# io-board-b-4.net
KiCad netlist of a schematic drawn in EAGLE
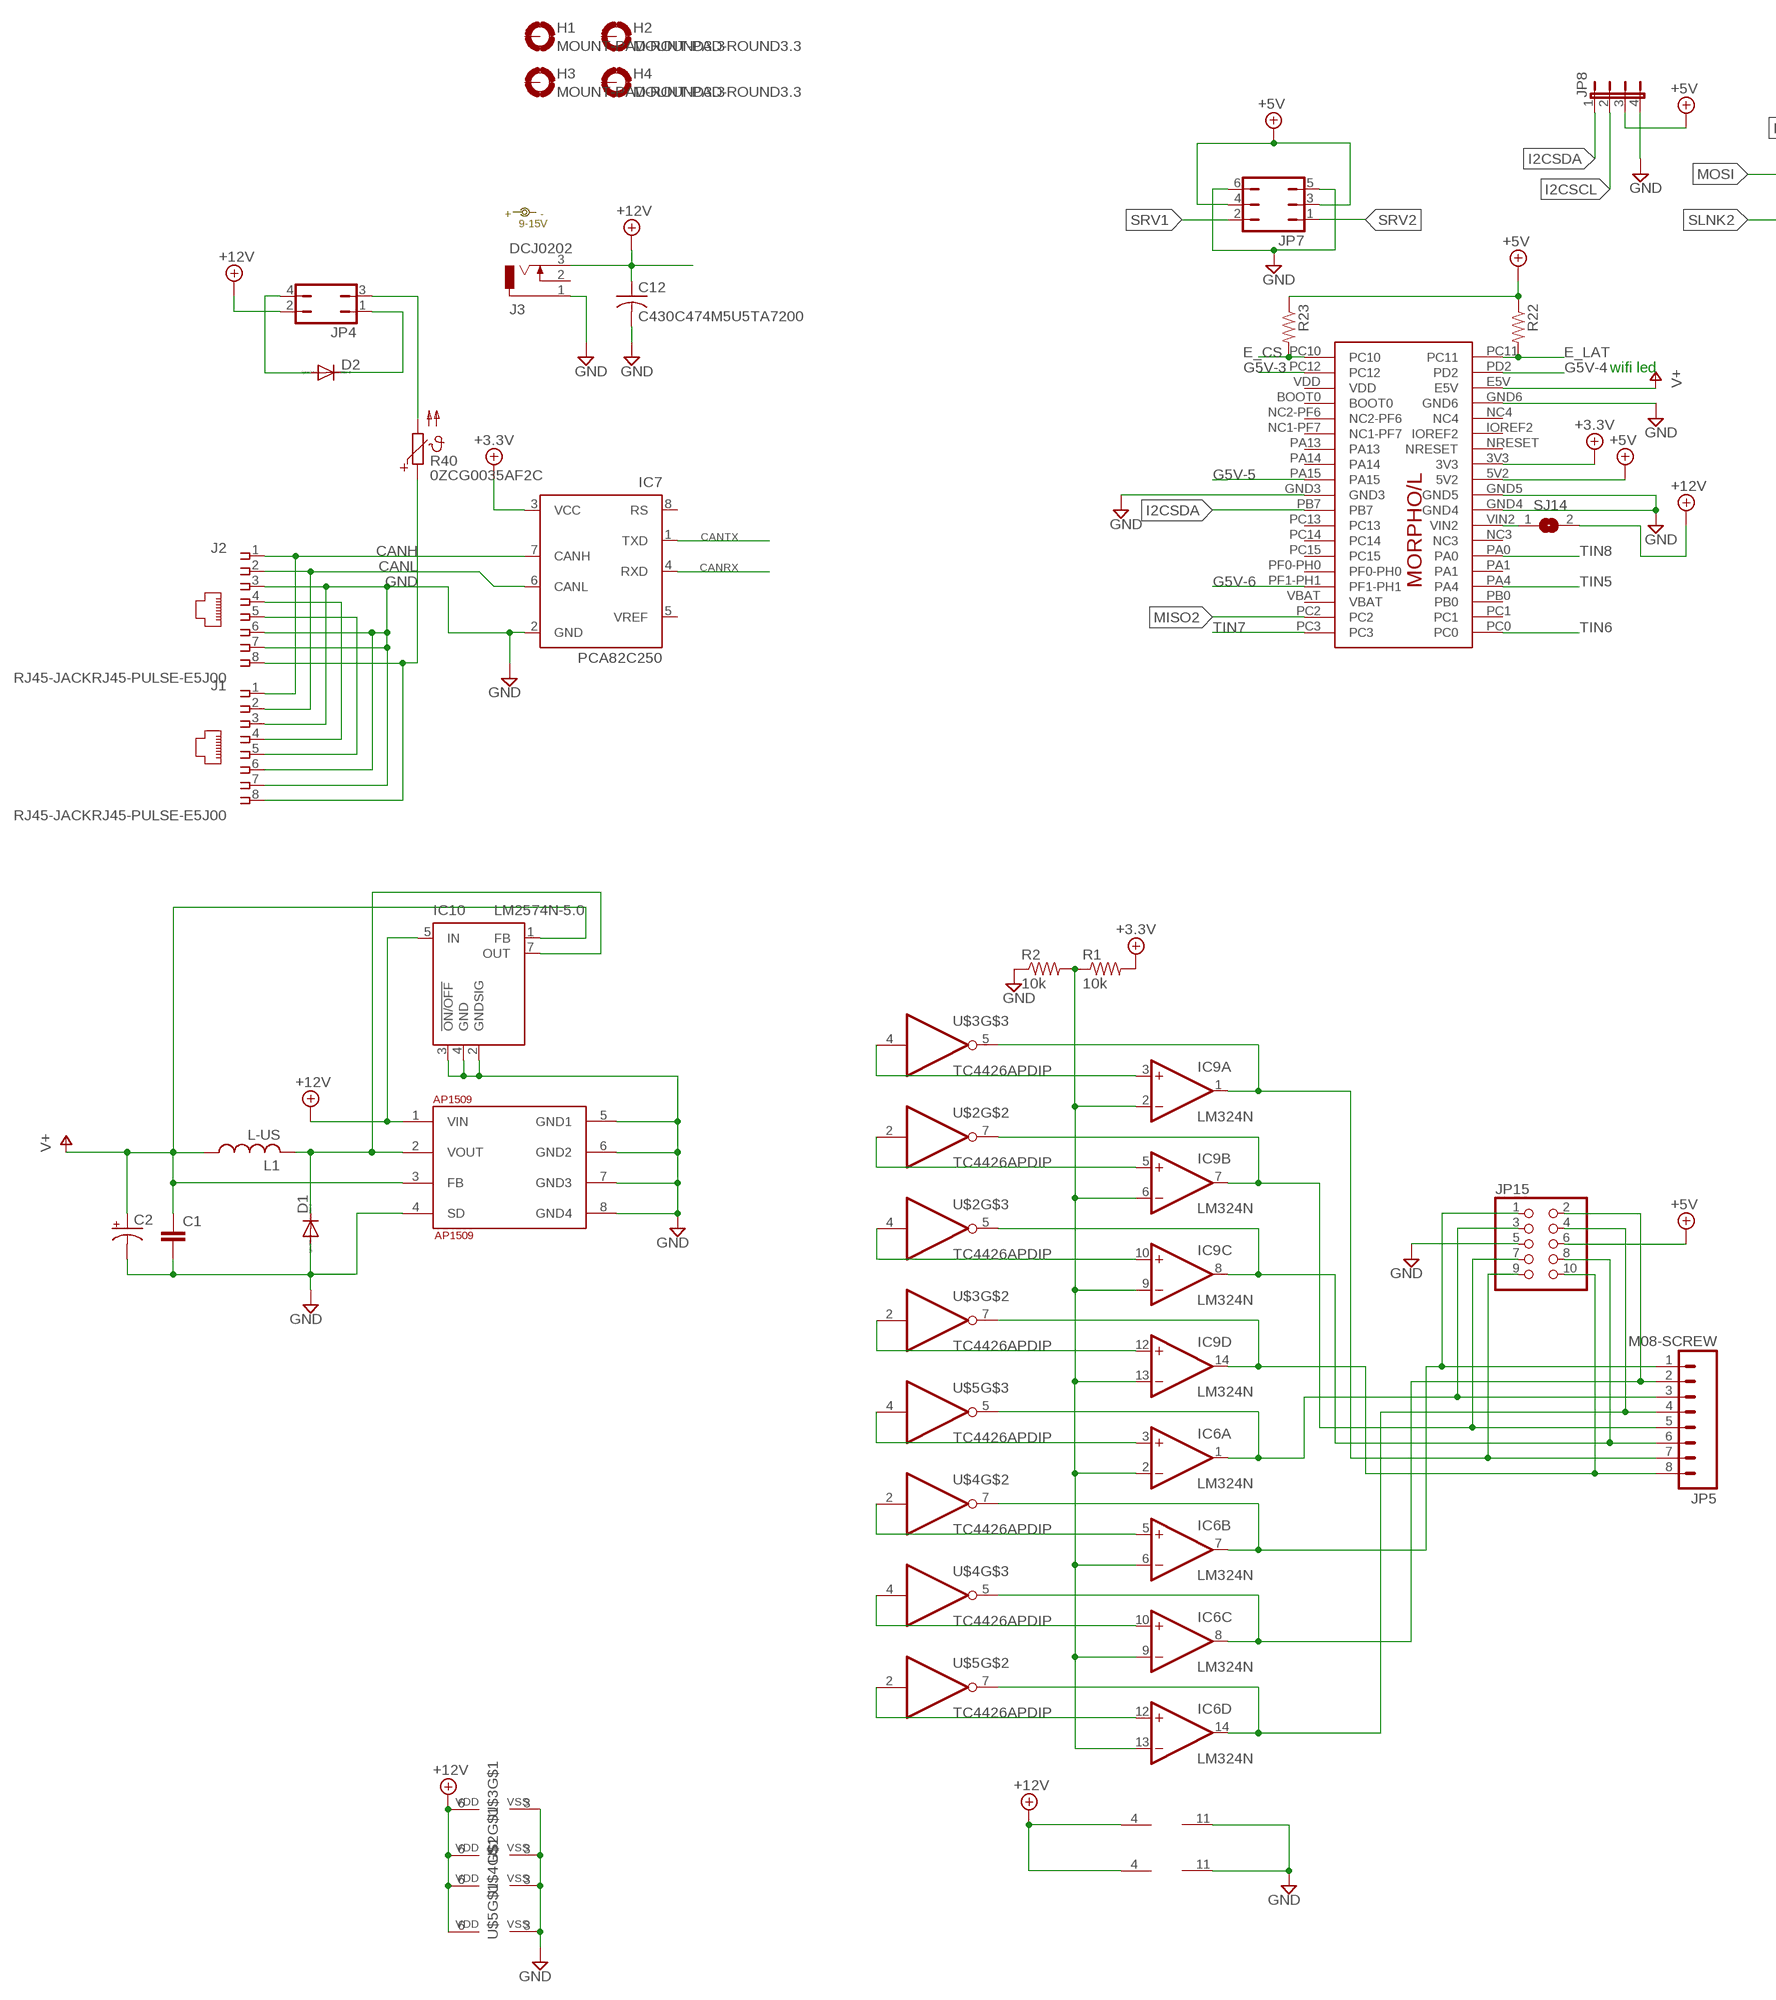
[diagram p0: schematic, sheet 1, part 1 of 2]
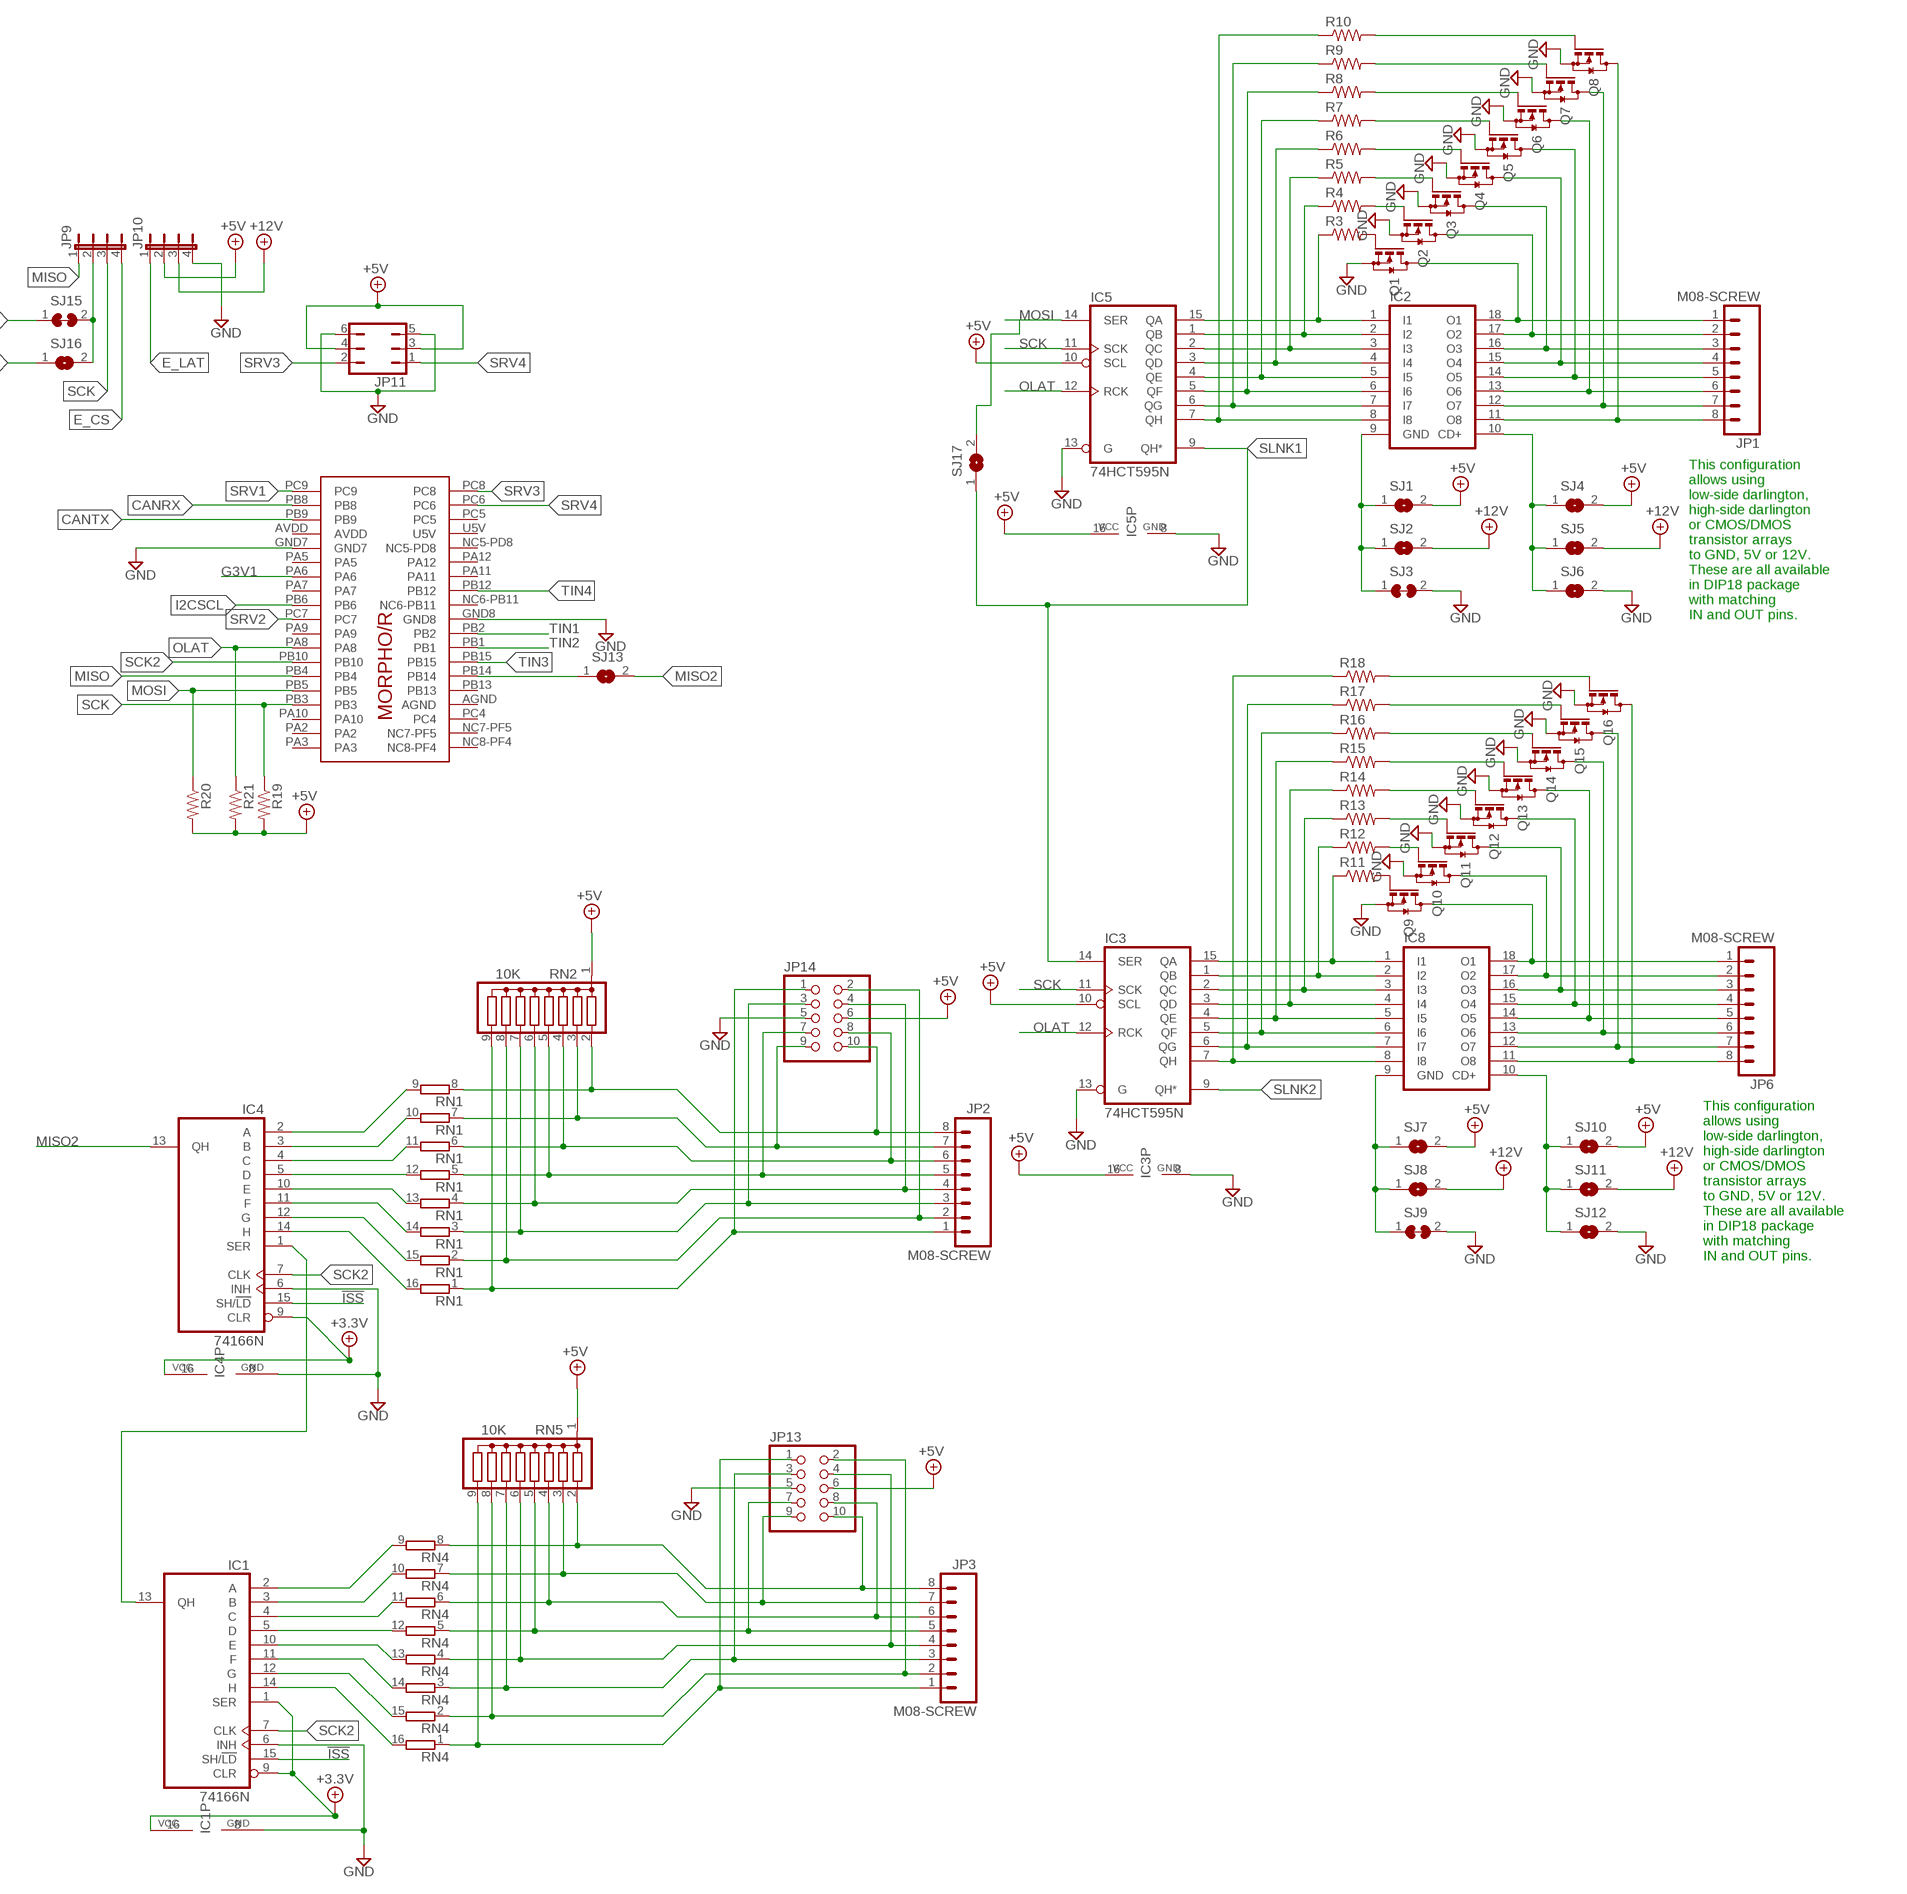
[diagram p1: schematic, sheet 1, part 2 of 2]

(export (version "E")
  (design (tool "Eeschema 10.0.6"))
  (components
    (comp (ref "+12V")
      (value "9-15V")
      (footprint "eagle-import:POWER_USAGE")
      (libsource (lib "eagle-import") (part "DOC-POWER_LABEL"))
    )
    (comp (ref "AP1509")
      (value "AP1509")
      (footprint "eagle-import:SO-08")
      (libsource (lib "eagle-import") (part "AP1509"))
    )
    (comp (ref "C1")
      (value "C-EUC1206")
      (footprint "eagle-import:C1206")
      (libsource (lib "eagle-import") (part "C-EUC1206"))
    )
    (comp (ref "C2")
      (value "CPOL-USE2.5-5")
      (footprint "eagle-import:E2,5-5")
      (libsource (lib "eagle-import") (part "CPOL-USE2.5-5"))
    )
    (comp (ref "C12")
      (value "C430C474M5U5TA7200")
      (footprint "eagle-import:C075-032X103")
      (libsource (lib "eagle-import") (part "C-US075-032X103"))
    )
    (comp (ref "D1")
      (value "DIODE-DO41-7.6")
      (footprint "eagle-import:DO41-7.6")
      (libsource (lib "eagle-import") (part "DIODE-DO41-7.6"))
    )
    (comp (ref "D2")
      (value "DIODE-DO41-7.6")
      (footprint "eagle-import:DO41-7.6")
      (libsource (lib "eagle-import") (part "DIODE-DO41-7.6"))
    )
    (comp (ref "H1")
      (value "MOUNT-PAD-ROUND3.3")
      (footprint "eagle-import:3,3-PAD")
      (libsource (lib "eagle-import") (part "MOUNT-PAD-ROUND3.3"))
    )
    (comp (ref "H2")
      (value "MOUNT-PAD-ROUND3.3")
      (footprint "eagle-import:3,3-PAD")
      (libsource (lib "eagle-import") (part "MOUNT-PAD-ROUND3.3"))
    )
    (comp (ref "H3")
      (value "MOUNT-PAD-ROUND3.3")
      (footprint "eagle-import:3,3-PAD")
      (libsource (lib "eagle-import") (part "MOUNT-PAD-ROUND3.3"))
    )
    (comp (ref "H4")
      (value "MOUNT-PAD-ROUND3.3")
      (footprint "eagle-import:3,3-PAD")
      (libsource (lib "eagle-import") (part "MOUNT-PAD-ROUND3.3"))
    )
    (comp (ref "IC1")
      (value "74166N")
      (footprint "eagle-import:DIL16")
      (libsource (lib "eagle-import") (part "74166N"))
    )
    (comp (ref "IC2")
      (value "ULN2803A")
      (footprint "eagle-import:DIL18-THIN")
      (libsource (lib "eagle-import") (part "ULN2803A"))
    )
    (comp (ref "IC3")
      (value "74HCT595N")
      (footprint "eagle-import:DIL16")
      (libsource (lib "eagle-import") (part "74595NHCT"))
    )
    (comp (ref "IC4")
      (value "74166N")
      (footprint "eagle-import:DIL16")
      (libsource (lib "eagle-import") (part "74166N"))
    )
    (comp (ref "IC5")
      (value "74HCT595N")
      (footprint "eagle-import:DIL16")
      (libsource (lib "eagle-import") (part "74595NHCT"))
    )
    (comp (ref "IC6")
      (value "LM324N")
      (footprint "eagle-import:DIL14")
      (libsource (lib "eagle-import") (part "LM324N"))
    )
    (comp (ref "IC7")
      (value "PCA82C250")
      (footprint "eagle-import:DIL08")
      (libsource (lib "eagle-import") (part "PCA82C250"))
    )
    (comp (ref "IC8")
      (value "ULN2803A")
      (footprint "eagle-import:DIL18-THIN")
      (libsource (lib "eagle-import") (part "ULN2803A"))
    )
    (comp (ref "IC9")
      (value "LM324N")
      (footprint "eagle-import:DIL14")
      (libsource (lib "eagle-import") (part "LM324N"))
    )
    (comp (ref "IC10")
      (value "LM2574N-5.0")
      (footprint "eagle-import:DIL08")
      (libsource (lib "eagle-import") (part "LM2574?-N5.0"))
    )
    (comp (ref "J1")
      (value "RJ45-JACKRJ45-PULSE-E5J00")
      (footprint "eagle-import:RJ45-PULSE-E5J88")
      (libsource (lib "eagle-import") (part "RJ45-JACKRJ45-PULSE-E5J00"))
    )
    (comp (ref "J2")
      (value "RJ45-JACKRJ45-PULSE-E5J00")
      (footprint "eagle-import:RJ45-PULSE-E5J88")
      (libsource (lib "eagle-import") (part "RJ45-JACKRJ45-PULSE-E5J00"))
    )
    (comp (ref "J3")
      (value "DCJ0202")
      (footprint "eagle-import:DCJ0202")
      (libsource (lib "eagle-import") (part "DCJ0202"))
    )
    (comp (ref "JP1")
      (value "M08-SCREW")
      (footprint "eagle-import:1X08_TERMINAL")
      (libsource (lib "eagle-import") (part "M08-SCREW"))
    )
    (comp (ref "JP2")
      (value "M08-SCREW")
      (footprint "eagle-import:1X08_TERMINAL")
      (libsource (lib "eagle-import") (part "M08-SCREW"))
    )
    (comp (ref "JP3")
      (value "M08-SCREW")
      (footprint "eagle-import:1X08_TERMINAL")
      (libsource (lib "eagle-import") (part "M08-SCREW"))
    )
    (comp (ref "JP4")
      (value "JP2Q")
      (footprint "eagle-import:JP2Q")
      (libsource (lib "eagle-import") (part "JP2Q"))
    )
    (comp (ref "JP5")
      (value "M08-SCREW")
      (footprint "eagle-import:1X08_TERMINAL")
      (libsource (lib "eagle-import") (part "M08-SCREW"))
    )
    (comp (ref "JP6")
      (value "M08-SCREW")
      (footprint "eagle-import:1X08_TERMINAL")
      (libsource (lib "eagle-import") (part "M08-SCREW"))
    )
    (comp (ref "JP7")
      (value "JP3Q")
      (footprint "eagle-import:JP3Q")
      (libsource (lib "eagle-import") (part "JP3Q"))
    )
    (comp (ref "JP8")
      (value "JP4-FLAT")
      (footprint "eagle-import:JP4F")
      (libsource (lib "eagle-import") (part "JP4-FLAT"))
    )
    (comp (ref "JP9")
      (value "JP4-FLAT")
      (footprint "eagle-import:JP4F")
      (libsource (lib "eagle-import") (part "JP4-FLAT"))
    )
    (comp (ref "JP10")
      (value "JP4-FLAT")
      (footprint "eagle-import:JP4F")
      (libsource (lib "eagle-import") (part "JP4-FLAT"))
    )
    (comp (ref "JP11")
      (value "JP3Q")
      (footprint "eagle-import:JP3Q")
      (libsource (lib "eagle-import") (part "JP3Q"))
    )
    (comp (ref "JP13")
      (value "PINHD-2X5CN")
      (footprint "eagle-import:CON10M")
      (libsource (lib "eagle-import") (part "PINHD-2X5CN"))
    )
    (comp (ref "JP14")
      (value "PINHD-2X5CN")
      (footprint "eagle-import:CON10M")
      (libsource (lib "eagle-import") (part "PINHD-2X5CN"))
    )
    (comp (ref "JP15")
      (value "PINHD-2X5CN")
      (footprint "eagle-import:CON10M")
      (libsource (lib "eagle-import") (part "PINHD-2X5CN"))
    )
    (comp (ref "L1")
      (value "L-US")
      (footprint "eagle-import:L5-8,5")
      (libsource (lib "eagle-import") (part "L-US"))
    )
    (comp (ref "Q1")
      (value "BSS123")
      (footprint "eagle-import:SOT23")
      (libsource (lib "eagle-import") (part "BSS123"))
    )
    (comp (ref "Q2")
      (value "BSS123")
      (footprint "eagle-import:SOT23")
      (libsource (lib "eagle-import") (part "BSS123"))
    )
    (comp (ref "Q3")
      (value "BSS123")
      (footprint "eagle-import:SOT23")
      (libsource (lib "eagle-import") (part "BSS123"))
    )
    (comp (ref "Q4")
      (value "BSS123")
      (footprint "eagle-import:SOT23")
      (libsource (lib "eagle-import") (part "BSS123"))
    )
    (comp (ref "Q5")
      (value "BSS123")
      (footprint "eagle-import:SOT23")
      (libsource (lib "eagle-import") (part "BSS123"))
    )
    (comp (ref "Q6")
      (value "BSS123")
      (footprint "eagle-import:SOT23")
      (libsource (lib "eagle-import") (part "BSS123"))
    )
    (comp (ref "Q7")
      (value "BSS123")
      (footprint "eagle-import:SOT23")
      (libsource (lib "eagle-import") (part "BSS123"))
    )
    (comp (ref "Q8")
      (value "BSS123")
      (footprint "eagle-import:SOT23")
      (libsource (lib "eagle-import") (part "BSS123"))
    )
    (comp (ref "Q9")
      (value "BSS123")
      (footprint "eagle-import:SOT23")
      (libsource (lib "eagle-import") (part "BSS123"))
    )
    (comp (ref "Q10")
      (value "BSS123")
      (footprint "eagle-import:SOT23")
      (libsource (lib "eagle-import") (part "BSS123"))
    )
    (comp (ref "Q11")
      (value "BSS123")
      (footprint "eagle-import:SOT23")
      (libsource (lib "eagle-import") (part "BSS123"))
    )
    (comp (ref "Q12")
      (value "BSS123")
      (footprint "eagle-import:SOT23")
      (libsource (lib "eagle-import") (part "BSS123"))
    )
    (comp (ref "Q13")
      (value "BSS123")
      (footprint "eagle-import:SOT23")
      (libsource (lib "eagle-import") (part "BSS123"))
    )
    (comp (ref "Q14")
      (value "BSS123")
      (footprint "eagle-import:SOT23")
      (libsource (lib "eagle-import") (part "BSS123"))
    )
    (comp (ref "Q15")
      (value "BSS123")
      (footprint "eagle-import:SOT23")
      (libsource (lib "eagle-import") (part "BSS123"))
    )
    (comp (ref "Q16")
      (value "BSS123")
      (footprint "eagle-import:SOT23")
      (libsource (lib "eagle-import") (part "BSS123"))
    )
    (comp (ref "R1")
      (value "10k")
      (footprint "eagle-import:R0805")
      (libsource (lib "eagle-import") (part "R-US_R0805"))
    )
    (comp (ref "R2")
      (value "10k")
      (footprint "eagle-import:R0805")
      (libsource (lib "eagle-import") (part "R-US_R0805"))
    )
    (comp (ref "R3")
      (value "R-US_R0603")
      (footprint "eagle-import:R0603")
      (libsource (lib "eagle-import") (part "R-US_R0603"))
    )
    (comp (ref "R4")
      (value "R-US_R0603")
      (footprint "eagle-import:R0603")
      (libsource (lib "eagle-import") (part "R-US_R0603"))
    )
    (comp (ref "R5")
      (value "R-US_R0603")
      (footprint "eagle-import:R0603")
      (libsource (lib "eagle-import") (part "R-US_R0603"))
    )
    (comp (ref "R6")
      (value "R-US_R0603")
      (footprint "eagle-import:R0603")
      (libsource (lib "eagle-import") (part "R-US_R0603"))
    )
    (comp (ref "R7")
      (value "R-US_R0603")
      (footprint "eagle-import:R0603")
      (libsource (lib "eagle-import") (part "R-US_R0603"))
    )
    (comp (ref "R8")
      (value "R-US_R0603")
      (footprint "eagle-import:R0603")
      (libsource (lib "eagle-import") (part "R-US_R0603"))
    )
    (comp (ref "R9")
      (value "R-US_R0603")
      (footprint "eagle-import:R0603")
      (libsource (lib "eagle-import") (part "R-US_R0603"))
    )
    (comp (ref "R10")
      (value "R-US_R0603")
      (footprint "eagle-import:R0603")
      (libsource (lib "eagle-import") (part "R-US_R0603"))
    )
    (comp (ref "R11")
      (value "R-US_R0603")
      (footprint "eagle-import:R0603")
      (libsource (lib "eagle-import") (part "R-US_R0603"))
    )
    (comp (ref "R12")
      (value "R-US_R0603")
      (footprint "eagle-import:R0603")
      (libsource (lib "eagle-import") (part "R-US_R0603"))
    )
    (comp (ref "R13")
      (value "R-US_R0603")
      (footprint "eagle-import:R0603")
      (libsource (lib "eagle-import") (part "R-US_R0603"))
    )
    (comp (ref "R14")
      (value "R-US_R0603")
      (footprint "eagle-import:R0603")
      (libsource (lib "eagle-import") (part "R-US_R0603"))
    )
    (comp (ref "R15")
      (value "R-US_R0603")
      (footprint "eagle-import:R0603")
      (libsource (lib "eagle-import") (part "R-US_R0603"))
    )
    (comp (ref "R16")
      (value "R-US_R0603")
      (footprint "eagle-import:R0603")
      (libsource (lib "eagle-import") (part "R-US_R0603"))
    )
    (comp (ref "R17")
      (value "R-US_R0603")
      (footprint "eagle-import:R0603")
      (libsource (lib "eagle-import") (part "R-US_R0603"))
    )
    (comp (ref "R18")
      (value "R-US_R0603")
      (footprint "eagle-import:R0603")
      (libsource (lib "eagle-import") (part "R-US_R0603"))
    )
    (comp (ref "R19")
      (value "R-US_R0805")
      (footprint "eagle-import:R0805")
      (libsource (lib "eagle-import") (part "rcl_334_R-US_R0805"))
    )
    (comp (ref "R20")
      (value "R-US_R0805")
      (footprint "eagle-import:R0805")
      (libsource (lib "eagle-import") (part "rcl_334_R-US_R0805"))
    )
    (comp (ref "R21")
      (value "R-US_R0805")
      (footprint "eagle-import:R0805")
      (libsource (lib "eagle-import") (part "rcl_334_R-US_R0805"))
    )
    (comp (ref "R22")
      (value "R-US_R0805")
      (footprint "eagle-import:R0805")
      (libsource (lib "eagle-import") (part "rcl_334_R-US_R0805"))
    )
    (comp (ref "R23")
      (value "R-US_R0805")
      (footprint "eagle-import:R0805")
      (libsource (lib "eagle-import") (part "rcl_334_R-US_R0805"))
    )
    (comp (ref "R40")
      (value "0ZCG0035AF2C")
      (footprint "eagle-import:PTC1812")
      (libsource (lib "eagle-import") (part "PTC_1812"))
    )
    (comp (ref "RN1")
      (value "8R-P")
      (footprint "eagle-import:DIL16")
      (libsource (lib "eagle-import") (part "8R-P"))
    )
    (comp (ref "RN2")
      (value "10K")
      (footprint "eagle-import:SIL9")
      (libsource (lib "eagle-import") (part "G08R"))
    )
    (comp (ref "RN4")
      (value "8R-P")
      (footprint "eagle-import:DIL16")
      (libsource (lib "eagle-import") (part "8R-P"))
    )
    (comp (ref "RN5")
      (value "10K")
      (footprint "eagle-import:SIL9")
      (libsource (lib "eagle-import") (part "G08R"))
    )
    (comp (ref "SJ1")
      (value "SJ")
      (footprint "eagle-import:SJ-RND")
      (libsource (lib "eagle-import") (part "SJ"))
    )
    (comp (ref "SJ2")
      (value "SJ")
      (footprint "eagle-import:SJ-RND")
      (libsource (lib "eagle-import") (part "SJ"))
    )
    (comp (ref "SJ3")
      (value "SJ-C")
      (footprint "eagle-import:SJW-C")
      (libsource (lib "eagle-import") (part "SJ-C"))
    )
    (comp (ref "SJ4")
      (value "SJ")
      (footprint "eagle-import:SJ-RND")
      (libsource (lib "eagle-import") (part "SJ"))
    )
    (comp (ref "SJ5")
      (value "SJ")
      (footprint "eagle-import:SJ-RND")
      (libsource (lib "eagle-import") (part "SJ"))
    )
    (comp (ref "SJ6")
      (value "SJ")
      (footprint "eagle-import:SJ-RND")
      (libsource (lib "eagle-import") (part "SJ"))
    )
    (comp (ref "SJ7")
      (value "SJ")
      (footprint "eagle-import:SJ-RND")
      (libsource (lib "eagle-import") (part "SJ"))
    )
    (comp (ref "SJ8")
      (value "SJ")
      (footprint "eagle-import:SJ-RND")
      (libsource (lib "eagle-import") (part "SJ"))
    )
    (comp (ref "SJ9")
      (value "SJ-C")
      (footprint "eagle-import:SJW-C")
      (libsource (lib "eagle-import") (part "SJ-C"))
    )
    (comp (ref "SJ10")
      (value "SJ")
      (footprint "eagle-import:SJ-RND")
      (libsource (lib "eagle-import") (part "SJ"))
    )
    (comp (ref "SJ11")
      (value "SJ")
      (footprint "eagle-import:SJ-RND")
      (libsource (lib "eagle-import") (part "SJ"))
    )
    (comp (ref "SJ12")
      (value "SJ")
      (footprint "eagle-import:SJ-RND")
      (libsource (lib "eagle-import") (part "SJ"))
    )
    (comp (ref "SJ13")
      (value "SJ")
      (footprint "eagle-import:SJ-RND")
      (libsource (lib "eagle-import") (part "SJ"))
    )
    (comp (ref "SJ14")
      (value "SJ")
      (footprint "eagle-import:SJ-RND")
      (libsource (lib "eagle-import") (part "SJ"))
    )
    (comp (ref "SJ15")
      (value "SJ-C")
      (footprint "eagle-import:SJW-C")
      (libsource (lib "eagle-import") (part "SJ-C"))
    )
    (comp (ref "SJ16")
      (value "SJ")
      (footprint "eagle-import:SJ-RND")
      (libsource (lib "eagle-import") (part "SJ"))
    )
    (comp (ref "SJ17")
      (value "SJ")
      (footprint "eagle-import:SJ-RND")
      (libsource (lib "eagle-import") (part "SJ"))
    )
    (comp (ref "U$1")
      (value "NUCLEO_64_GENERIC")
      (footprint "eagle-import:NUCLEO_BRD_BASE64")
      (libsource (lib "eagle-import") (part "NUCLEO_64_GENERIC"))
    )
    (comp (ref "U$2")
      (value "TC4426APDIP")
      (footprint "eagle-import:DIL08-LONG")
      (libsource (lib "eagle-import") (part "TC4426APDIP"))
    )
    (comp (ref "U$3")
      (value "TC4426APDIP")
      (footprint "eagle-import:DIL08-LONG")
      (libsource (lib "eagle-import") (part "TC4426APDIP"))
    )
    (comp (ref "U$4")
      (value "TC4426APDIP")
      (footprint "eagle-import:DIL08-LONG")
      (libsource (lib "eagle-import") (part "TC4426APDIP"))
    )
    (comp (ref "U$5")
      (value "TC4426APDIP")
      (footprint "eagle-import:DIL08-LONG")
      (libsource (lib "eagle-import") (part "TC4426APDIP"))
    )
  )
  (nets
    (net (code "1") (name "+3.3V") (class "Default")
      (node (ref "IC1") (pin "1") (pinfunction "SER_1") (pintype "input"))
      (node (ref "IC1") (pin "16") (pinfunction "VCC_16") (pintype "power_in"))
      (node (ref "IC1") (pin "9") (pinfunction "CLR_9") (pintype "input"))
      (node (ref "IC4") (pin "16") (pinfunction "VCC_16") (pintype "power_in"))
      (node (ref "IC4") (pin "9") (pinfunction "CLR_9") (pintype "input"))
      (node (ref "IC7") (pin "3") (pinfunction "VCC_3") (pintype "power_in"))
      (node (ref "R1") (pin "2") (pinfunction "2_2") (pintype "passive"))
      (node (ref "U$1") (pin "3V3") (pinfunction "3V3_3V3") (pintype "power_in"))
    )
    (net (code "2") (name "+5V") (class "Default")
      (node (ref "IC3") (pin "10") (pinfunction "SCL_10") (pintype "input"))
      (node (ref "IC3") (pin "16") (pinfunction "VCC_16") (pintype "power_in"))
      (node (ref "IC5") (pin "10") (pinfunction "SCL_10") (pintype "input"))
      (node (ref "IC5") (pin "16") (pinfunction "VCC_16") (pintype "power_in"))
      (node (ref "JP10") (pin "2") (pinfunction "2_2") (pintype "passive"))
      (node (ref "JP11") (pin "3") (pinfunction "3_3") (pintype "passive"))
      (node (ref "JP11") (pin "4") (pinfunction "4_4") (pintype "passive"))
      (node (ref "JP13") (pin "6") (pinfunction "6_6") (pintype "passive"))
      (node (ref "JP14") (pin "6") (pinfunction "6_6") (pintype "passive"))
      (node (ref "JP15") (pin "6") (pinfunction "6_6") (pintype "passive"))
      (node (ref "JP7") (pin "3") (pinfunction "3_3") (pintype "passive"))
      (node (ref "JP7") (pin "4") (pinfunction "4_4") (pintype "passive"))
      (node (ref "JP8") (pin "3") (pinfunction "3_3") (pintype "passive"))
      (node (ref "R19") (pin "2") (pinfunction "2_2") (pintype "passive"))
      (node (ref "R20") (pin "2") (pinfunction "2_2") (pintype "passive"))
      (node (ref "R21") (pin "2") (pinfunction "2_2") (pintype "passive"))
      (node (ref "R22") (pin "1") (pinfunction "1_1") (pintype "passive"))
      (node (ref "R23") (pin "1") (pinfunction "1_1") (pintype "passive"))
      (node (ref "RN2") (pin "1") (pinfunction "1_1") (pintype "passive"))
      (node (ref "RN5") (pin "1") (pinfunction "1_1") (pintype "passive"))
      (node (ref "SJ1") (pin "2") (pinfunction "2_2") (pintype "passive"))
      (node (ref "SJ10") (pin "2") (pinfunction "2_2") (pintype "passive"))
      (node (ref "SJ4") (pin "2") (pinfunction "2_2") (pintype "passive"))
      (node (ref "SJ7") (pin "2") (pinfunction "2_2") (pintype "passive"))
      (node (ref "U$1") (pin "5V2") (pinfunction "5V2_5V2") (pintype "power_in"))
    )
    (net (code "3") (name "+12V") (class "Default")
      (node (ref "AP1509") (pin "1") (pinfunction "VIN_1") (pintype "bidirectional"))
      (node (ref "C12") (pin "1") (pinfunction "1_1") (pintype "passive"))
      (node (ref "IC10") (pin "5") (pinfunction "IN_5") (pintype "input"))
      (node (ref "IC6") (pin "4") (pinfunction "V+_4") (pintype "power_in"))
      (node (ref "IC9") (pin "4") (pinfunction "V+_4") (pintype "power_in"))
      (node (ref "J3") (pin "3") (pinfunction "3_3") (pintype "passive"))
      (node (ref "JP10") (pin "3") (pinfunction "3_3") (pintype "passive"))
      (node (ref "JP4") (pin "2") (pinfunction "2_2") (pintype "passive"))
      (node (ref "SJ11") (pin "2") (pinfunction "2_2") (pintype "passive"))
      (node (ref "SJ14") (pin "2") (pinfunction "2_2") (pintype "passive"))
      (node (ref "SJ2") (pin "2") (pinfunction "2_2") (pintype "passive"))
      (node (ref "SJ5") (pin "2") (pinfunction "2_2") (pintype "passive"))
      (node (ref "SJ8") (pin "2") (pinfunction "2_2") (pintype "passive"))
      (node (ref "U$2") (pin "6") (pinfunction "VDD_6") (pintype "power_in"))
      (node (ref "U$3") (pin "6") (pinfunction "VDD_6") (pintype "power_in"))
      (node (ref "U$4") (pin "6") (pinfunction "VDD_6") (pintype "power_in"))
      (node (ref "U$5") (pin "6") (pinfunction "VDD_6") (pintype "power_in"))
    )
    (net (code "4") (name "/AGND") (class "Default")
      (node (ref "U$1") (pin "AGND") (pinfunction "AGND_AGND") (pintype "power_in"))
    )
    (net (code "5") (name "/AVDD") (class "Default")
      (node (ref "U$1") (pin "AVDD") (pinfunction "AVDD_AVDD") (pintype "power_in"))
    )
    (net (code "6") (name "/CANH") (class "Default")
      (node (ref "IC7") (pin "7") (pinfunction "CANH_7") (pintype "bidirectional"))
      (node (ref "J1") (pin "1") (pinfunction "1_1") (pintype "passive"))
      (node (ref "J2") (pin "1") (pinfunction "1_1") (pintype "passive"))
    )
    (net (code "7") (name "/CANL") (class "Default")
      (node (ref "IC7") (pin "6") (pinfunction "CANL_6") (pintype "bidirectional"))
      (node (ref "J1") (pin "2") (pinfunction "2_2") (pintype "passive"))
      (node (ref "J2") (pin "2") (pinfunction "2_2") (pintype "passive"))
    )
    (net (code "8") (name "/G3V1") (class "Default")
      (node (ref "U$1") (pin "PA6") (pinfunction "PA6_PA6") (pintype "bidirectional"))
    )
    (net (code "9") (name "/G5V-3") (class "Default")
      (node (ref "U$1") (pin "PC12") (pinfunction "PC12_PC12") (pintype "bidirectional"))
    )
    (net (code "10") (name "/G5V-4") (class "Default")
      (node (ref "U$1") (pin "PD2") (pinfunction "PD2_PD2") (pintype "bidirectional"))
    )
    (net (code "11") (name "/G5V-5") (class "Default")
      (node (ref "U$1") (pin "PA15") (pinfunction "PA15_PA15") (pintype "bidirectional"))
    )
    (net (code "12") (name "/G5V-6") (class "Default")
      (node (ref "U$1") (pin "PF1-PH1") (pinfunction "PF1-PH1_PF1-PH1") (pintype "bidirectional"))
    )
    (net (code "13") (name "/TIN1") (class "Default")
      (node (ref "IC9") (pin "3") (pinfunction "+IN_3") (pintype "input"))
      (node (ref "U$1") (pin "PB2") (pinfunction "PB2_PB2") (pintype "bidirectional"))
      (node (ref "U$3") (pin "4") (pinfunction "I_4") (pintype "input"))
    )
    (net (code "14") (name "/TIN2") (class "Default")
      (node (ref "IC9") (pin "5") (pinfunction "+IN_5") (pintype "input"))
      (node (ref "U$1") (pin "PB1") (pinfunction "PB1_PB1") (pintype "bidirectional"))
      (node (ref "U$2") (pin "2") (pinfunction "I_2") (pintype "input"))
    )
    (net (code "15") (name "/TIN5") (class "Default")
      (node (ref "IC6") (pin "3") (pinfunction "+IN_3") (pintype "input"))
      (node (ref "U$1") (pin "PA4") (pinfunction "PA4_PA4") (pintype "bidirectional"))
      (node (ref "U$5") (pin "4") (pinfunction "I_4") (pintype "input"))
    )
    (net (code "16") (name "/TIN6") (class "Default")
      (node (ref "IC6") (pin "5") (pinfunction "+IN_5") (pintype "input"))
      (node (ref "U$1") (pin "PC0") (pinfunction "PC0_PC0") (pintype "bidirectional"))
      (node (ref "U$4") (pin "2") (pinfunction "I_2") (pintype "input"))
    )
    (net (code "17") (name "/TIN7") (class "Default")
      (node (ref "IC6") (pin "10") (pinfunction "+IN_10") (pintype "input"))
      (node (ref "U$1") (pin "PC3") (pinfunction "PC3_PC3") (pintype "bidirectional"))
      (node (ref "U$4") (pin "4") (pinfunction "I_4") (pintype "input"))
    )
    (net (code "18") (name "/TIN8") (class "Default")
      (node (ref "IC6") (pin "12") (pinfunction "+IN_12") (pintype "input"))
      (node (ref "U$1") (pin "PA0") (pinfunction "PA0_PA0") (pintype "bidirectional"))
      (node (ref "U$5") (pin "2") (pinfunction "I_2") (pintype "input"))
    )
    (net (code "19") (name "/U5V") (class "Default")
      (node (ref "U$1") (pin "U5V") (pinfunction "U5V_U5V") (pintype "power_in"))
    )
    (net (code "20") (name "/VBAT") (class "Default")
      (node (ref "U$1") (pin "VBAT") (pinfunction "VBAT_VBAT") (pintype "power_in"))
    )
    (net (code "21") (name "/VDD") (class "Default")
      (node (ref "U$1") (pin "VDD") (pinfunction "VDD_VDD") (pintype "power_in"))
    )
    (net (code "22") (name "/~{ISS}") (class "Default")
      (node (ref "IC1") (pin "15") (pinfunction "SH/~{LD}_15") (pintype "input"))
      (node (ref "IC4") (pin "15") (pinfunction "SH/~{LD}_15") (pintype "input"))
    )
    (net (code "23") (name "CANRX") (class "Default")
      (node (ref "IC7") (pin "4") (pinfunction "RXD_4") (pintype "output"))
      (node (ref "U$1") (pin "PB8") (pinfunction "PB8_PB8") (pintype "bidirectional"))
    )
    (net (code "24") (name "CANTX") (class "Default")
      (node (ref "IC7") (pin "1") (pinfunction "TXD_1") (pintype "input"))
      (node (ref "U$1") (pin "PB9") (pinfunction "PB9_PB9") (pintype "bidirectional"))
    )
    (net (code "25") (name "E_CS") (class "Default")
      (node (ref "JP9") (pin "4") (pinfunction "4_4") (pintype "passive"))
      (node (ref "R23") (pin "2") (pinfunction "2_2") (pintype "passive"))
      (node (ref "U$1") (pin "PC10") (pinfunction "PC10_PC10") (pintype "bidirectional"))
    )
    (net (code "26") (name "E_LAT") (class "Default")
      (node (ref "JP10") (pin "1") (pinfunction "1_1") (pintype "passive"))
      (node (ref "R22") (pin "2") (pinfunction "2_2") (pintype "passive"))
      (node (ref "U$1") (pin "PC11") (pinfunction "PC11_PC11") (pintype "bidirectional"))
    )
    (net (code "27") (name "GND") (class "Default")
      (node (ref "AP1509") (pin "4") (pinfunction "SD_4") (pintype "bidirectional"))
      (node (ref "AP1509") (pin "5") (pinfunction "GND1_5") (pintype "power_in"))
      (node (ref "AP1509") (pin "6") (pinfunction "GND2_6") (pintype "power_in"))
      (node (ref "AP1509") (pin "7") (pinfunction "GND3_7") (pintype "power_in"))
      (node (ref "AP1509") (pin "8") (pinfunction "GND4_8") (pintype "power_in"))
      (node (ref "C1") (pin "2") (pinfunction "2_2") (pintype "passive"))
      (node (ref "C12") (pin "2") (pinfunction "2_2") (pintype "passive"))
      (node (ref "C2") (pin "-") (pinfunction "-_-") (pintype "passive"))
      (node (ref "D1") (pin "A") (pinfunction "A_A") (pintype "passive"))
      (node (ref "IC1") (pin "6") (pinfunction "INH_6") (pintype "input"))
      (node (ref "IC1") (pin "8") (pinfunction "GND_8") (pintype "power_in"))
      (node (ref "IC10") (pin "2") (pinfunction "GNDSIG_2") (pintype "input"))
      (node (ref "IC10") (pin "3") (pinfunction "~{ON/OFF}_3") (pintype "input"))
      (node (ref "IC10") (pin "4") (pinfunction "GND_4") (pintype "power_in"))
      (node (ref "IC3") (pin "13") (pinfunction "G_13") (pintype "input"))
      (node (ref "IC3") (pin "8") (pinfunction "GND_8") (pintype "power_in"))
      (node (ref "IC4") (pin "6") (pinfunction "INH_6") (pintype "input"))
      (node (ref "IC4") (pin "8") (pinfunction "GND_8") (pintype "power_in"))
      (node (ref "IC5") (pin "13") (pinfunction "G_13") (pintype "input"))
      (node (ref "IC5") (pin "8") (pinfunction "GND_8") (pintype "power_in"))
      (node (ref "IC6") (pin "11") (pinfunction "V-_11") (pintype "power_in"))
      (node (ref "IC7") (pin "2") (pinfunction "GND_2") (pintype "power_in"))
      (node (ref "IC9") (pin "11") (pinfunction "V-_11") (pintype "power_in"))
      (node (ref "J1") (pin "3") (pinfunction "3_3") (pintype "passive"))
      (node (ref "J1") (pin "6") (pinfunction "6_6") (pintype "passive"))
      (node (ref "J1") (pin "7") (pinfunction "7_7") (pintype "passive"))
      (node (ref "J2") (pin "3") (pinfunction "3_3") (pintype "passive"))
      (node (ref "J2") (pin "6") (pinfunction "6_6") (pintype "passive"))
      (node (ref "J2") (pin "7") (pinfunction "7_7") (pintype "passive"))
      (node (ref "J3") (pin "1") (pinfunction "1_1") (pintype "passive"))
      (node (ref "JP10") (pin "4") (pinfunction "4_4") (pintype "passive"))
      (node (ref "JP11") (pin "5") (pinfunction "5_5") (pintype "passive"))
      (node (ref "JP11") (pin "6") (pinfunction "6_6") (pintype "passive"))
      (node (ref "JP13") (pin "5") (pinfunction "5_5") (pintype "passive"))
      (node (ref "JP14") (pin "5") (pinfunction "5_5") (pintype "passive"))
      (node (ref "JP15") (pin "5") (pinfunction "5_5") (pintype "passive"))
      (node (ref "JP7") (pin "5") (pinfunction "5_5") (pintype "passive"))
      (node (ref "JP7") (pin "6") (pinfunction "6_6") (pintype "passive"))
      (node (ref "JP8") (pin "4") (pinfunction "4_4") (pintype "passive"))
      (node (ref "Q1") (pin "2") (pinfunction "S_2") (pintype "passive"))
      (node (ref "Q10") (pin "2") (pinfunction "S_2") (pintype "passive"))
      (node (ref "Q11") (pin "2") (pinfunction "S_2") (pintype "passive"))
      (node (ref "Q12") (pin "2") (pinfunction "S_2") (pintype "passive"))
      (node (ref "Q13") (pin "2") (pinfunction "S_2") (pintype "passive"))
      (node (ref "Q14") (pin "2") (pinfunction "S_2") (pintype "passive"))
      (node (ref "Q15") (pin "2") (pinfunction "S_2") (pintype "passive"))
      (node (ref "Q16") (pin "2") (pinfunction "S_2") (pintype "passive"))
      (node (ref "Q2") (pin "2") (pinfunction "S_2") (pintype "passive"))
      (node (ref "Q3") (pin "2") (pinfunction "S_2") (pintype "passive"))
      (node (ref "Q4") (pin "2") (pinfunction "S_2") (pintype "passive"))
      (node (ref "Q5") (pin "2") (pinfunction "S_2") (pintype "passive"))
      (node (ref "Q6") (pin "2") (pinfunction "S_2") (pintype "passive"))
      (node (ref "Q7") (pin "2") (pinfunction "S_2") (pintype "passive"))
      (node (ref "Q8") (pin "2") (pinfunction "S_2") (pintype "passive"))
      (node (ref "Q9") (pin "2") (pinfunction "S_2") (pintype "passive"))
      (node (ref "R2") (pin "1") (pinfunction "1_1") (pintype "passive"))
      (node (ref "SJ12") (pin "2") (pinfunction "2_2") (pintype "passive"))
      (node (ref "SJ3") (pin "2") (pinfunction "2_2") (pintype "passive"))
      (node (ref "SJ6") (pin "2") (pinfunction "2_2") (pintype "passive"))
      (node (ref "SJ9") (pin "2") (pinfunction "2_2") (pintype "passive"))
      (node (ref "U$1") (pin "GND3") (pinfunction "GND3_GND3") (pintype "power_in"))
      (node (ref "U$1") (pin "GND4") (pinfunction "GND4_GND4") (pintype "power_in"))
      (node (ref "U$1") (pin "GND5") (pinfunction "GND5_GND5") (pintype "power_in"))
      (node (ref "U$1") (pin "GND6") (pinfunction "GND6_GND6") (pintype "power_in"))
      (node (ref "U$1") (pin "GND7") (pinfunction "GND7_GND7") (pintype "power_in"))
      (node (ref "U$1") (pin "GND8") (pinfunction "GND8_GND8") (pintype "power_in"))
      (node (ref "U$2") (pin "3") (pinfunction "VSS_3") (pintype "power_in"))
      (node (ref "U$3") (pin "3") (pinfunction "VSS_3") (pintype "power_in"))
      (node (ref "U$4") (pin "3") (pinfunction "VSS_3") (pintype "power_in"))
      (node (ref "U$5") (pin "3") (pinfunction "VSS_3") (pintype "power_in"))
    )
    (net (code "28") (name "I2CSCL") (class "Default")
      (node (ref "JP8") (pin "2") (pinfunction "2_2") (pintype "passive"))
      (node (ref "U$1") (pin "PB6") (pinfunction "PB6_PB6") (pintype "bidirectional"))
    )
    (net (code "29") (name "I2CSDA") (class "Default")
      (node (ref "JP8") (pin "1") (pinfunction "1_1") (pintype "passive"))
      (node (ref "U$1") (pin "PB7") (pinfunction "PB7_PB7") (pintype "bidirectional"))
    )
    (net (code "30") (name "MISO") (class "Default")
      (node (ref "JP9") (pin "1") (pinfunction "1_1") (pintype "passive"))
      (node (ref "U$1") (pin "PB4") (pinfunction "PB4_PB4") (pintype "bidirectional"))
    )
    (net (code "31") (name "MISO2") (class "Default")
      (node (ref "IC4") (pin "13") (pinfunction "QH_13") (pintype "output"))
      (node (ref "SJ13") (pin "2") (pinfunction "2_2") (pintype "passive"))
      (node (ref "U$1") (pin "PC2") (pinfunction "PC2_PC2") (pintype "bidirectional"))
    )
    (net (code "32") (name "MOSI") (class "Default")
      (node (ref "IC5") (pin "14") (pinfunction "SER_14") (pintype "input"))
      (node (ref "R20") (pin "1") (pinfunction "1_1") (pintype "passive"))
      (node (ref "SJ15") (pin "1") (pinfunction "1_1") (pintype "passive"))
      (node (ref "SJ17") (pin "2") (pinfunction "2_2") (pintype "passive"))
      (node (ref "U$1") (pin "PB5") (pinfunction "PB5_PB5") (pintype "bidirectional"))
    )
    (net (code "33") (name "Net-(AP1509-VOUT)") (class "Default")
      (node (ref "AP1509") (pin "2") (pinfunction "VOUT_2") (pintype "bidirectional"))
      (node (ref "D1") (pin "C") (pinfunction "C_C") (pintype "passive"))
      (node (ref "IC10") (pin "7") (pinfunction "OUT_7") (pintype "passive"))
      (node (ref "L1") (pin "2") (pinfunction "2_2") (pintype "passive"))
    )
    (net (code "34") (name "Net-(D2-PadA)") (class "Default")
      (node (ref "D2") (pin "A") (pinfunction "A_A") (pintype "passive"))
      (node (ref "JP4") (pin "4") (pinfunction "4_4") (pintype "passive"))
    )
    (net (code "35") (name "Net-(D2-PadC)") (class "Default")
      (node (ref "D2") (pin "C") (pinfunction "C_C") (pintype "passive"))
      (node (ref "JP4") (pin "1") (pinfunction "1_1") (pintype "passive"))
    )
    (net (code "36") (name "Net-(IC1A-A)") (class "Default")
      (node (ref "IC1") (pin "2") (pinfunction "A_2") (pintype "input"))
      (node (ref "RN4") (pin "9") (pinfunction "2_9") (pintype "passive"))
    )
    (net (code "37") (name "Net-(IC1A-B)") (class "Default")
      (node (ref "IC1") (pin "3") (pinfunction "B_3") (pintype "input"))
      (node (ref "RN4") (pin "10") (pinfunction "2_10") (pintype "passive"))
    )
    (net (code "38") (name "Net-(IC1A-C)") (class "Default")
      (node (ref "IC1") (pin "4") (pinfunction "C_4") (pintype "input"))
      (node (ref "RN4") (pin "11") (pinfunction "2_11") (pintype "passive"))
    )
    (net (code "39") (name "Net-(IC1A-D)") (class "Default")
      (node (ref "IC1") (pin "5") (pinfunction "D_5") (pintype "input"))
      (node (ref "RN4") (pin "12") (pinfunction "2_12") (pintype "passive"))
    )
    (net (code "40") (name "Net-(IC1A-E)") (class "Default")
      (node (ref "IC1") (pin "10") (pinfunction "E_10") (pintype "input"))
      (node (ref "RN4") (pin "13") (pinfunction "2_13") (pintype "passive"))
    )
    (net (code "41") (name "Net-(IC1A-F)") (class "Default")
      (node (ref "IC1") (pin "11") (pinfunction "F_11") (pintype "input"))
      (node (ref "RN4") (pin "14") (pinfunction "2_14") (pintype "passive"))
    )
    (net (code "42") (name "Net-(IC1A-G)") (class "Default")
      (node (ref "IC1") (pin "12") (pinfunction "G_12") (pintype "input"))
      (node (ref "RN4") (pin "15") (pinfunction "2_15") (pintype "passive"))
    )
    (net (code "43") (name "Net-(IC1A-H)") (class "Default")
      (node (ref "IC1") (pin "14") (pinfunction "H_14") (pintype "input"))
      (node (ref "RN4") (pin "16") (pinfunction "2_16") (pintype "passive"))
    )
    (net (code "44") (name "Net-(IC1A-QH)") (class "Default")
      (node (ref "IC1") (pin "13") (pinfunction "QH_13") (pintype "output"))
      (node (ref "IC4") (pin "1") (pinfunction "SER_1") (pintype "input"))
    )
    (net (code "45") (name "Net-(IC2-CD+)") (class "Default")
      (node (ref "IC2") (pin "10") (pinfunction "CD+_10") (pintype "passive"))
      (node (ref "SJ4") (pin "1") (pinfunction "1_1") (pintype "passive"))
      (node (ref "SJ5") (pin "1") (pinfunction "1_1") (pintype "passive"))
      (node (ref "SJ6") (pin "1") (pinfunction "1_1") (pintype "passive"))
    )
    (net (code "46") (name "Net-(IC2-GND)") (class "Default")
      (node (ref "IC2") (pin "9") (pinfunction "GND_9") (pintype "power_in"))
      (node (ref "SJ1") (pin "1") (pinfunction "1_1") (pintype "passive"))
      (node (ref "SJ2") (pin "1") (pinfunction "1_1") (pintype "passive"))
      (node (ref "SJ3") (pin "1") (pinfunction "1_1") (pintype "passive"))
    )
    (net (code "47") (name "Net-(IC2-I1)") (class "Default")
      (node (ref "IC2") (pin "1") (pinfunction "I1_1") (pintype "input"))
      (node (ref "IC5") (pin "15") (pinfunction "QA_15") (pintype "tri_state"))
      (node (ref "R3") (pin "1") (pinfunction "1_1") (pintype "passive"))
    )
    (net (code "48") (name "Net-(IC2-I2)") (class "Default")
      (node (ref "IC2") (pin "2") (pinfunction "I2_2") (pintype "input"))
      (node (ref "IC5") (pin "1") (pinfunction "QB_1") (pintype "tri_state"))
      (node (ref "R4") (pin "1") (pinfunction "1_1") (pintype "passive"))
    )
    (net (code "49") (name "Net-(IC2-I3)") (class "Default")
      (node (ref "IC2") (pin "3") (pinfunction "I3_3") (pintype "input"))
      (node (ref "IC5") (pin "2") (pinfunction "QC_2") (pintype "tri_state"))
      (node (ref "R5") (pin "1") (pinfunction "1_1") (pintype "passive"))
    )
    (net (code "50") (name "Net-(IC2-I4)") (class "Default")
      (node (ref "IC2") (pin "4") (pinfunction "I4_4") (pintype "input"))
      (node (ref "IC5") (pin "3") (pinfunction "QD_3") (pintype "tri_state"))
      (node (ref "R6") (pin "1") (pinfunction "1_1") (pintype "passive"))
    )
    (net (code "51") (name "Net-(IC2-I5)") (class "Default")
      (node (ref "IC2") (pin "5") (pinfunction "I5_5") (pintype "input"))
      (node (ref "IC5") (pin "4") (pinfunction "QE_4") (pintype "tri_state"))
      (node (ref "R7") (pin "1") (pinfunction "1_1") (pintype "passive"))
    )
    (net (code "52") (name "Net-(IC2-I6)") (class "Default")
      (node (ref "IC2") (pin "6") (pinfunction "I6_6") (pintype "input"))
      (node (ref "IC5") (pin "5") (pinfunction "QF_5") (pintype "tri_state"))
      (node (ref "R8") (pin "1") (pinfunction "1_1") (pintype "passive"))
    )
    (net (code "53") (name "Net-(IC2-I7)") (class "Default")
      (node (ref "IC2") (pin "7") (pinfunction "I7_7") (pintype "input"))
      (node (ref "IC5") (pin "6") (pinfunction "QG_6") (pintype "tri_state"))
      (node (ref "R9") (pin "1") (pinfunction "1_1") (pintype "passive"))
    )
    (net (code "54") (name "Net-(IC2-I8)") (class "Default")
      (node (ref "IC2") (pin "8") (pinfunction "I8_8") (pintype "input"))
      (node (ref "IC5") (pin "7") (pinfunction "QH_7") (pintype "tri_state"))
      (node (ref "R10") (pin "1") (pinfunction "1_1") (pintype "passive"))
    )
    (net (code "55") (name "Net-(IC2-O1)") (class "Default")
      (node (ref "IC2") (pin "18") (pinfunction "O1_18") (pintype "open_collector"))
      (node (ref "JP1") (pin "1") (pinfunction "1_1") (pintype "passive"))
      (node (ref "Q1") (pin "3") (pinfunction "D_3") (pintype "passive"))
    )
    (net (code "56") (name "Net-(IC2-O2)") (class "Default")
      (node (ref "IC2") (pin "17") (pinfunction "O2_17") (pintype "open_collector"))
      (node (ref "JP1") (pin "2") (pinfunction "2_2") (pintype "passive"))
      (node (ref "Q2") (pin "3") (pinfunction "D_3") (pintype "passive"))
    )
    (net (code "57") (name "Net-(IC2-O3)") (class "Default")
      (node (ref "IC2") (pin "16") (pinfunction "O3_16") (pintype "open_collector"))
      (node (ref "JP1") (pin "3") (pinfunction "3_3") (pintype "passive"))
      (node (ref "Q3") (pin "3") (pinfunction "D_3") (pintype "passive"))
    )
    (net (code "58") (name "Net-(IC2-O4)") (class "Default")
      (node (ref "IC2") (pin "15") (pinfunction "O4_15") (pintype "open_collector"))
      (node (ref "JP1") (pin "4") (pinfunction "4_4") (pintype "passive"))
      (node (ref "Q4") (pin "3") (pinfunction "D_3") (pintype "passive"))
    )
    (net (code "59") (name "Net-(IC2-O5)") (class "Default")
      (node (ref "IC2") (pin "14") (pinfunction "O5_14") (pintype "open_collector"))
      (node (ref "JP1") (pin "5") (pinfunction "5_5") (pintype "passive"))
      (node (ref "Q5") (pin "3") (pinfunction "D_3") (pintype "passive"))
    )
    (net (code "60") (name "Net-(IC2-O6)") (class "Default")
      (node (ref "IC2") (pin "13") (pinfunction "O6_13") (pintype "open_collector"))
      (node (ref "JP1") (pin "6") (pinfunction "6_6") (pintype "passive"))
      (node (ref "Q6") (pin "3") (pinfunction "D_3") (pintype "passive"))
    )
    (net (code "61") (name "Net-(IC2-O7)") (class "Default")
      (node (ref "IC2") (pin "12") (pinfunction "O7_12") (pintype "open_collector"))
      (node (ref "JP1") (pin "7") (pinfunction "7_7") (pintype "passive"))
      (node (ref "Q7") (pin "3") (pinfunction "D_3") (pintype "passive"))
    )
    (net (code "62") (name "Net-(IC2-O8)") (class "Default")
      (node (ref "IC2") (pin "11") (pinfunction "O8_11") (pintype "open_collector"))
      (node (ref "JP1") (pin "8") (pinfunction "8_8") (pintype "passive"))
      (node (ref "Q8") (pin "3") (pinfunction "D_3") (pintype "passive"))
    )
    (net (code "63") (name "Net-(IC3A-QA)") (class "Default")
      (node (ref "IC3") (pin "15") (pinfunction "QA_15") (pintype "tri_state"))
      (node (ref "IC8") (pin "1") (pinfunction "I1_1") (pintype "input"))
      (node (ref "R11") (pin "1") (pinfunction "1_1") (pintype "passive"))
    )
    (net (code "64") (name "Net-(IC3A-QB)") (class "Default")
      (node (ref "IC3") (pin "1") (pinfunction "QB_1") (pintype "tri_state"))
      (node (ref "IC8") (pin "2") (pinfunction "I2_2") (pintype "input"))
      (node (ref "R12") (pin "1") (pinfunction "1_1") (pintype "passive"))
    )
    (net (code "65") (name "Net-(IC3A-QC)") (class "Default")
      (node (ref "IC3") (pin "2") (pinfunction "QC_2") (pintype "tri_state"))
      (node (ref "IC8") (pin "3") (pinfunction "I3_3") (pintype "input"))
      (node (ref "R13") (pin "1") (pinfunction "1_1") (pintype "passive"))
    )
    (net (code "66") (name "Net-(IC3A-QD)") (class "Default")
      (node (ref "IC3") (pin "3") (pinfunction "QD_3") (pintype "tri_state"))
      (node (ref "IC8") (pin "4") (pinfunction "I4_4") (pintype "input"))
      (node (ref "R14") (pin "1") (pinfunction "1_1") (pintype "passive"))
    )
    (net (code "67") (name "Net-(IC3A-QE)") (class "Default")
      (node (ref "IC3") (pin "4") (pinfunction "QE_4") (pintype "tri_state"))
      (node (ref "IC8") (pin "5") (pinfunction "I5_5") (pintype "input"))
      (node (ref "R15") (pin "1") (pinfunction "1_1") (pintype "passive"))
    )
    (net (code "68") (name "Net-(IC3A-QF)") (class "Default")
      (node (ref "IC3") (pin "5") (pinfunction "QF_5") (pintype "tri_state"))
      (node (ref "IC8") (pin "6") (pinfunction "I6_6") (pintype "input"))
      (node (ref "R16") (pin "1") (pinfunction "1_1") (pintype "passive"))
    )
    (net (code "69") (name "Net-(IC3A-QG)") (class "Default")
      (node (ref "IC3") (pin "6") (pinfunction "QG_6") (pintype "tri_state"))
      (node (ref "IC8") (pin "7") (pinfunction "I7_7") (pintype "input"))
      (node (ref "R17") (pin "1") (pinfunction "1_1") (pintype "passive"))
    )
    (net (code "70") (name "Net-(IC3A-QH)") (class "Default")
      (node (ref "IC3") (pin "7") (pinfunction "QH_7") (pintype "tri_state"))
      (node (ref "IC8") (pin "8") (pinfunction "I8_8") (pintype "input"))
      (node (ref "R18") (pin "1") (pinfunction "1_1") (pintype "passive"))
    )
    (net (code "71") (name "Net-(IC4A-A)") (class "Default")
      (node (ref "IC4") (pin "2") (pinfunction "A_2") (pintype "input"))
      (node (ref "RN1") (pin "9") (pinfunction "2_9") (pintype "passive"))
    )
    (net (code "72") (name "Net-(IC4A-B)") (class "Default")
      (node (ref "IC4") (pin "3") (pinfunction "B_3") (pintype "input"))
      (node (ref "RN1") (pin "10") (pinfunction "2_10") (pintype "passive"))
    )
    (net (code "73") (name "Net-(IC4A-C)") (class "Default")
      (node (ref "IC4") (pin "4") (pinfunction "C_4") (pintype "input"))
      (node (ref "RN1") (pin "11") (pinfunction "2_11") (pintype "passive"))
    )
    (net (code "74") (name "Net-(IC4A-D)") (class "Default")
      (node (ref "IC4") (pin "5") (pinfunction "D_5") (pintype "input"))
      (node (ref "RN1") (pin "12") (pinfunction "2_12") (pintype "passive"))
    )
    (net (code "75") (name "Net-(IC4A-E)") (class "Default")
      (node (ref "IC4") (pin "10") (pinfunction "E_10") (pintype "input"))
      (node (ref "RN1") (pin "13") (pinfunction "2_13") (pintype "passive"))
    )
    (net (code "76") (name "Net-(IC4A-F)") (class "Default")
      (node (ref "IC4") (pin "11") (pinfunction "F_11") (pintype "input"))
      (node (ref "RN1") (pin "14") (pinfunction "2_14") (pintype "passive"))
    )
    (net (code "77") (name "Net-(IC4A-G)") (class "Default")
      (node (ref "IC4") (pin "12") (pinfunction "G_12") (pintype "input"))
      (node (ref "RN1") (pin "15") (pinfunction "2_15") (pintype "passive"))
    )
    (net (code "78") (name "Net-(IC4A-H)") (class "Default")
      (node (ref "IC4") (pin "14") (pinfunction "H_14") (pintype "input"))
      (node (ref "RN1") (pin "16") (pinfunction "2_16") (pintype "passive"))
    )
    (net (code "79") (name "Net-(IC6A--IN)") (class "Default")
      (node (ref "IC6") (pin "13") (pinfunction "-IN_13") (pintype "input"))
      (node (ref "IC6") (pin "2") (pinfunction "-IN_2") (pintype "input"))
      (node (ref "IC6") (pin "6") (pinfunction "-IN_6") (pintype "input"))
      (node (ref "IC6") (pin "9") (pinfunction "-IN_9") (pintype "input"))
      (node (ref "IC9") (pin "13") (pinfunction "-IN_13") (pintype "input"))
      (node (ref "IC9") (pin "2") (pinfunction "-IN_2") (pintype "input"))
      (node (ref "IC9") (pin "6") (pinfunction "-IN_6") (pintype "input"))
      (node (ref "IC9") (pin "9") (pinfunction "-IN_9") (pintype "input"))
      (node (ref "R1") (pin "1") (pinfunction "1_1") (pintype "passive"))
      (node (ref "R2") (pin "2") (pinfunction "2_2") (pintype "passive"))
    )
    (net (code "80") (name "Net-(IC6A-OUT)") (class "Default")
      (node (ref "IC6") (pin "1") (pinfunction "OUT_1") (pintype "output"))
      (node (ref "JP15") (pin "3") (pinfunction "3_3") (pintype "passive"))
      (node (ref "JP5") (pin "3") (pinfunction "3_3") (pintype "passive"))
      (node (ref "U$5") (pin "5") (pinfunction "O_5") (pintype "output"))
    )
    (net (code "81") (name "Net-(IC6B-OUT)") (class "Default")
      (node (ref "IC6") (pin "7") (pinfunction "OUT_7") (pintype "output"))
      (node (ref "JP15") (pin "1") (pinfunction "1_1") (pintype "passive"))
      (node (ref "JP5") (pin "1") (pinfunction "1_1") (pintype "passive"))
      (node (ref "U$4") (pin "7") (pinfunction "O_7") (pintype "output"))
    )
    (net (code "82") (name "Net-(IC6C-OUT)") (class "Default")
      (node (ref "IC6") (pin "8") (pinfunction "OUT_8") (pintype "output"))
      (node (ref "JP15") (pin "2") (pinfunction "2_2") (pintype "passive"))
      (node (ref "JP5") (pin "2") (pinfunction "2_2") (pintype "passive"))
      (node (ref "U$4") (pin "5") (pinfunction "O_5") (pintype "output"))
    )
    (net (code "83") (name "Net-(IC6D-OUT)") (class "Default")
      (node (ref "IC6") (pin "14") (pinfunction "OUT_14") (pintype "output"))
      (node (ref "JP15") (pin "4") (pinfunction "4_4") (pintype "passive"))
      (node (ref "JP5") (pin "4") (pinfunction "4_4") (pintype "passive"))
      (node (ref "U$5") (pin "7") (pinfunction "O_7") (pintype "output"))
    )
    (net (code "84") (name "Net-(IC8-CD+)") (class "Default")
      (node (ref "IC8") (pin "10") (pinfunction "CD+_10") (pintype "passive"))
      (node (ref "SJ10") (pin "1") (pinfunction "1_1") (pintype "passive"))
      (node (ref "SJ11") (pin "1") (pinfunction "1_1") (pintype "passive"))
      (node (ref "SJ12") (pin "1") (pinfunction "1_1") (pintype "passive"))
    )
    (net (code "85") (name "Net-(IC8-GND)") (class "Default")
      (node (ref "IC8") (pin "9") (pinfunction "GND_9") (pintype "power_in"))
      (node (ref "SJ7") (pin "1") (pinfunction "1_1") (pintype "passive"))
      (node (ref "SJ8") (pin "1") (pinfunction "1_1") (pintype "passive"))
      (node (ref "SJ9") (pin "1") (pinfunction "1_1") (pintype "passive"))
    )
    (net (code "86") (name "Net-(IC8-O1)") (class "Default")
      (node (ref "IC8") (pin "18") (pinfunction "O1_18") (pintype "open_collector"))
      (node (ref "JP6") (pin "1") (pinfunction "1_1") (pintype "passive"))
      (node (ref "Q9") (pin "3") (pinfunction "D_3") (pintype "passive"))
    )
    (net (code "87") (name "Net-(IC8-O2)") (class "Default")
      (node (ref "IC8") (pin "17") (pinfunction "O2_17") (pintype "open_collector"))
      (node (ref "JP6") (pin "2") (pinfunction "2_2") (pintype "passive"))
      (node (ref "Q10") (pin "3") (pinfunction "D_3") (pintype "passive"))
    )
    (net (code "88") (name "Net-(IC8-O3)") (class "Default")
      (node (ref "IC8") (pin "16") (pinfunction "O3_16") (pintype "open_collector"))
      (node (ref "JP6") (pin "3") (pinfunction "3_3") (pintype "passive"))
      (node (ref "Q11") (pin "3") (pinfunction "D_3") (pintype "passive"))
    )
    (net (code "89") (name "Net-(IC8-O4)") (class "Default")
      (node (ref "IC8") (pin "15") (pinfunction "O4_15") (pintype "open_collector"))
      (node (ref "JP6") (pin "4") (pinfunction "4_4") (pintype "passive"))
      (node (ref "Q12") (pin "3") (pinfunction "D_3") (pintype "passive"))
    )
    (net (code "90") (name "Net-(IC8-O5)") (class "Default")
      (node (ref "IC8") (pin "14") (pinfunction "O5_14") (pintype "open_collector"))
      (node (ref "JP6") (pin "5") (pinfunction "5_5") (pintype "passive"))
      (node (ref "Q13") (pin "3") (pinfunction "D_3") (pintype "passive"))
    )
    (net (code "91") (name "Net-(IC8-O6)") (class "Default")
      (node (ref "IC8") (pin "13") (pinfunction "O6_13") (pintype "open_collector"))
      (node (ref "JP6") (pin "6") (pinfunction "6_6") (pintype "passive"))
      (node (ref "Q14") (pin "3") (pinfunction "D_3") (pintype "passive"))
    )
    (net (code "92") (name "Net-(IC8-O7)") (class "Default")
      (node (ref "IC8") (pin "12") (pinfunction "O7_12") (pintype "open_collector"))
      (node (ref "JP6") (pin "7") (pinfunction "7_7") (pintype "passive"))
      (node (ref "Q15") (pin "3") (pinfunction "D_3") (pintype "passive"))
    )
    (net (code "93") (name "Net-(IC8-O8)") (class "Default")
      (node (ref "IC8") (pin "11") (pinfunction "O8_11") (pintype "open_collector"))
      (node (ref "JP6") (pin "8") (pinfunction "8_8") (pintype "passive"))
      (node (ref "Q16") (pin "3") (pinfunction "D_3") (pintype "passive"))
    )
    (net (code "94") (name "Net-(IC9A-OUT)") (class "Default")
      (node (ref "IC9") (pin "1") (pinfunction "OUT_1") (pintype "output"))
      (node (ref "JP15") (pin "9") (pinfunction "9_9") (pintype "passive"))
      (node (ref "JP5") (pin "7") (pinfunction "7_7") (pintype "passive"))
      (node (ref "U$3") (pin "5") (pinfunction "O_5") (pintype "output"))
    )
    (net (code "95") (name "Net-(IC9B-OUT)") (class "Default")
      (node (ref "IC9") (pin "7") (pinfunction "OUT_7") (pintype "output"))
      (node (ref "JP15") (pin "7") (pinfunction "7_7") (pintype "passive"))
      (node (ref "JP5") (pin "5") (pinfunction "5_5") (pintype "passive"))
      (node (ref "U$2") (pin "7") (pinfunction "O_7") (pintype "output"))
    )
    (net (code "96") (name "Net-(IC9C-OUT)") (class "Default")
      (node (ref "IC9") (pin "8") (pinfunction "OUT_8") (pintype "output"))
      (node (ref "JP15") (pin "8") (pinfunction "8_8") (pintype "passive"))
      (node (ref "JP5") (pin "6") (pinfunction "6_6") (pintype "passive"))
      (node (ref "U$2") (pin "5") (pinfunction "O_5") (pintype "output"))
    )
    (net (code "97") (name "Net-(IC9D-OUT)") (class "Default")
      (node (ref "IC9") (pin "14") (pinfunction "OUT_14") (pintype "output"))
      (node (ref "JP15") (pin "10") (pinfunction "10_10") (pintype "passive"))
      (node (ref "JP5") (pin "8") (pinfunction "8_8") (pintype "passive"))
      (node (ref "U$3") (pin "7") (pinfunction "O_7") (pintype "output"))
    )
    (net (code "98") (name "Net-(J1-Pad4)") (class "Default")
      (node (ref "J1") (pin "4") (pinfunction "4_4") (pintype "passive"))
      (node (ref "J2") (pin "4") (pinfunction "4_4") (pintype "passive"))
    )
    (net (code "99") (name "Net-(J1-Pad5)") (class "Default")
      (node (ref "J1") (pin "5") (pinfunction "5_5") (pintype "passive"))
      (node (ref "J2") (pin "5") (pinfunction "5_5") (pintype "passive"))
    )
    (net (code "100") (name "Net-(J1-Pad8)") (class "Default")
      (node (ref "J1") (pin "8") (pinfunction "8_8") (pintype "passive"))
      (node (ref "J2") (pin "8") (pinfunction "8_8") (pintype "passive"))
      (node (ref "R40") (pin "1") (pinfunction "1_1") (pintype "passive"))
    )
    (net (code "101") (name "Net-(JP4-Pad3)") (class "Default")
      (node (ref "JP4") (pin "3") (pinfunction "3_3") (pintype "passive"))
      (node (ref "R40") (pin "2") (pinfunction "2_2") (pintype "passive"))
    )
    (net (code "102") (name "Net-(JP9-Pad2)") (class "Default")
      (node (ref "JP9") (pin "2") (pinfunction "2_2") (pintype "passive"))
      (node (ref "SJ15") (pin "2") (pinfunction "2_2") (pintype "passive"))
      (node (ref "SJ16") (pin "2") (pinfunction "2_2") (pintype "passive"))
    )
    (net (code "103") (name "Net-(JP13-Pad1)") (class "Default")
      (node (ref "JP13") (pin "1") (pinfunction "1_1") (pintype "passive"))
      (node (ref "JP3") (pin "1") (pinfunction "1_1") (pintype "passive"))
      (node (ref "RN4") (pin "1") (pinfunction "1_1") (pintype "passive"))
      (node (ref "RN5") (pin "9") (pinfunction "9_9") (pintype "passive"))
    )
    (net (code "104") (name "Net-(JP14-Pad1)") (class "Default")
      (node (ref "JP14") (pin "1") (pinfunction "1_1") (pintype "passive"))
      (node (ref "JP2") (pin "1") (pinfunction "1_1") (pintype "passive"))
      (node (ref "RN1") (pin "1") (pinfunction "1_1") (pintype "passive"))
      (node (ref "RN2") (pin "9") (pinfunction "9_9") (pintype "passive"))
    )
    (net (code "105") (name "Net-(Q1-G)") (class "Default")
      (node (ref "Q1") (pin "1") (pinfunction "G_1") (pintype "passive"))
      (node (ref "R3") (pin "2") (pinfunction "2_2") (pintype "passive"))
    )
    (net (code "106") (name "Net-(Q2-G)") (class "Default")
      (node (ref "Q2") (pin "1") (pinfunction "G_1") (pintype "passive"))
      (node (ref "R4") (pin "2") (pinfunction "2_2") (pintype "passive"))
    )
    (net (code "107") (name "Net-(Q3-G)") (class "Default")
      (node (ref "Q3") (pin "1") (pinfunction "G_1") (pintype "passive"))
      (node (ref "R5") (pin "2") (pinfunction "2_2") (pintype "passive"))
    )
    (net (code "108") (name "Net-(Q4-G)") (class "Default")
      (node (ref "Q4") (pin "1") (pinfunction "G_1") (pintype "passive"))
      (node (ref "R6") (pin "2") (pinfunction "2_2") (pintype "passive"))
    )
    (net (code "109") (name "Net-(Q5-G)") (class "Default")
      (node (ref "Q5") (pin "1") (pinfunction "G_1") (pintype "passive"))
      (node (ref "R7") (pin "2") (pinfunction "2_2") (pintype "passive"))
    )
    (net (code "110") (name "Net-(Q6-G)") (class "Default")
      (node (ref "Q6") (pin "1") (pinfunction "G_1") (pintype "passive"))
      (node (ref "R8") (pin "2") (pinfunction "2_2") (pintype "passive"))
    )
    (net (code "111") (name "Net-(Q7-G)") (class "Default")
      (node (ref "Q7") (pin "1") (pinfunction "G_1") (pintype "passive"))
      (node (ref "R9") (pin "2") (pinfunction "2_2") (pintype "passive"))
    )
    (net (code "112") (name "Net-(Q8-G)") (class "Default")
      (node (ref "Q8") (pin "1") (pinfunction "G_1") (pintype "passive"))
      (node (ref "R10") (pin "2") (pinfunction "2_2") (pintype "passive"))
    )
    (net (code "113") (name "Net-(Q9-G)") (class "Default")
      (node (ref "Q9") (pin "1") (pinfunction "G_1") (pintype "passive"))
      (node (ref "R11") (pin "2") (pinfunction "2_2") (pintype "passive"))
    )
    (net (code "114") (name "Net-(Q10-G)") (class "Default")
      (node (ref "Q10") (pin "1") (pinfunction "G_1") (pintype "passive"))
      (node (ref "R12") (pin "2") (pinfunction "2_2") (pintype "passive"))
    )
    (net (code "115") (name "Net-(Q11-G)") (class "Default")
      (node (ref "Q11") (pin "1") (pinfunction "G_1") (pintype "passive"))
      (node (ref "R13") (pin "2") (pinfunction "2_2") (pintype "passive"))
    )
    (net (code "116") (name "Net-(Q12-G)") (class "Default")
      (node (ref "Q12") (pin "1") (pinfunction "G_1") (pintype "passive"))
      (node (ref "R14") (pin "2") (pinfunction "2_2") (pintype "passive"))
    )
    (net (code "117") (name "Net-(Q13-G)") (class "Default")
      (node (ref "Q13") (pin "1") (pinfunction "G_1") (pintype "passive"))
      (node (ref "R15") (pin "2") (pinfunction "2_2") (pintype "passive"))
    )
    (net (code "118") (name "Net-(Q14-G)") (class "Default")
      (node (ref "Q14") (pin "1") (pinfunction "G_1") (pintype "passive"))
      (node (ref "R16") (pin "2") (pinfunction "2_2") (pintype "passive"))
    )
    (net (code "119") (name "Net-(Q15-G)") (class "Default")
      (node (ref "Q15") (pin "1") (pinfunction "G_1") (pintype "passive"))
      (node (ref "R17") (pin "2") (pinfunction "2_2") (pintype "passive"))
    )
    (net (code "120") (name "Net-(Q16-G)") (class "Default")
      (node (ref "Q16") (pin "1") (pinfunction "G_1") (pintype "passive"))
      (node (ref "R18") (pin "2") (pinfunction "2_2") (pintype "passive"))
    )
    (net (code "121") (name "Net-(RN1B-1)") (class "Default")
      (node (ref "JP14") (pin "2") (pinfunction "2_2") (pintype "passive"))
      (node (ref "JP2") (pin "2") (pinfunction "2_2") (pintype "passive"))
      (node (ref "RN1") (pin "2") (pinfunction "1_2") (pintype "passive"))
      (node (ref "RN2") (pin "8") (pinfunction "8_8") (pintype "passive"))
    )
    (net (code "122") (name "Net-(RN1C-1)") (class "Default")
      (node (ref "JP14") (pin "3") (pinfunction "3_3") (pintype "passive"))
      (node (ref "JP2") (pin "3") (pinfunction "3_3") (pintype "passive"))
      (node (ref "RN1") (pin "3") (pinfunction "1_3") (pintype "passive"))
      (node (ref "RN2") (pin "7") (pinfunction "7_7") (pintype "passive"))
    )
    (net (code "123") (name "Net-(RN1D-1)") (class "Default")
      (node (ref "JP14") (pin "4") (pinfunction "4_4") (pintype "passive"))
      (node (ref "JP2") (pin "4") (pinfunction "4_4") (pintype "passive"))
      (node (ref "RN1") (pin "4") (pinfunction "1_4") (pintype "passive"))
      (node (ref "RN2") (pin "6") (pinfunction "6_6") (pintype "passive"))
    )
    (net (code "124") (name "Net-(RN1E-1)") (class "Default")
      (node (ref "JP14") (pin "7") (pinfunction "7_7") (pintype "passive"))
      (node (ref "JP2") (pin "5") (pinfunction "5_5") (pintype "passive"))
      (node (ref "RN1") (pin "5") (pinfunction "1_5") (pintype "passive"))
      (node (ref "RN2") (pin "5") (pinfunction "5_5") (pintype "passive"))
    )
    (net (code "125") (name "Net-(RN1F-1)") (class "Default")
      (node (ref "JP14") (pin "8") (pinfunction "8_8") (pintype "passive"))
      (node (ref "JP2") (pin "6") (pinfunction "6_6") (pintype "passive"))
      (node (ref "RN1") (pin "6") (pinfunction "1_6") (pintype "passive"))
      (node (ref "RN2") (pin "4") (pinfunction "4_4") (pintype "passive"))
    )
    (net (code "126") (name "Net-(RN1G-1)") (class "Default")
      (node (ref "JP14") (pin "9") (pinfunction "9_9") (pintype "passive"))
      (node (ref "JP2") (pin "7") (pinfunction "7_7") (pintype "passive"))
      (node (ref "RN1") (pin "7") (pinfunction "1_7") (pintype "passive"))
      (node (ref "RN2") (pin "3") (pinfunction "3_3") (pintype "passive"))
    )
    (net (code "127") (name "Net-(RN1H-1)") (class "Default")
      (node (ref "JP14") (pin "10") (pinfunction "10_10") (pintype "passive"))
      (node (ref "JP2") (pin "8") (pinfunction "8_8") (pintype "passive"))
      (node (ref "RN1") (pin "8") (pinfunction "1_8") (pintype "passive"))
      (node (ref "RN2") (pin "2") (pinfunction "2_2") (pintype "passive"))
    )
    (net (code "128") (name "Net-(RN4B-1)") (class "Default")
      (node (ref "JP13") (pin "2") (pinfunction "2_2") (pintype "passive"))
      (node (ref "JP3") (pin "2") (pinfunction "2_2") (pintype "passive"))
      (node (ref "RN4") (pin "2") (pinfunction "1_2") (pintype "passive"))
      (node (ref "RN5") (pin "8") (pinfunction "8_8") (pintype "passive"))
    )
    (net (code "129") (name "Net-(RN4C-1)") (class "Default")
      (node (ref "JP13") (pin "3") (pinfunction "3_3") (pintype "passive"))
      (node (ref "JP3") (pin "3") (pinfunction "3_3") (pintype "passive"))
      (node (ref "RN4") (pin "3") (pinfunction "1_3") (pintype "passive"))
      (node (ref "RN5") (pin "7") (pinfunction "7_7") (pintype "passive"))
    )
    (net (code "130") (name "Net-(RN4D-1)") (class "Default")
      (node (ref "JP13") (pin "4") (pinfunction "4_4") (pintype "passive"))
      (node (ref "JP3") (pin "4") (pinfunction "4_4") (pintype "passive"))
      (node (ref "RN4") (pin "4") (pinfunction "1_4") (pintype "passive"))
      (node (ref "RN5") (pin "6") (pinfunction "6_6") (pintype "passive"))
    )
    (net (code "131") (name "Net-(RN4E-1)") (class "Default")
      (node (ref "JP13") (pin "7") (pinfunction "7_7") (pintype "passive"))
      (node (ref "JP3") (pin "5") (pinfunction "5_5") (pintype "passive"))
      (node (ref "RN4") (pin "5") (pinfunction "1_5") (pintype "passive"))
      (node (ref "RN5") (pin "5") (pinfunction "5_5") (pintype "passive"))
    )
    (net (code "132") (name "Net-(RN4F-1)") (class "Default")
      (node (ref "JP13") (pin "8") (pinfunction "8_8") (pintype "passive"))
      (node (ref "JP3") (pin "6") (pinfunction "6_6") (pintype "passive"))
      (node (ref "RN4") (pin "6") (pinfunction "1_6") (pintype "passive"))
      (node (ref "RN5") (pin "4") (pinfunction "4_4") (pintype "passive"))
    )
    (net (code "133") (name "Net-(RN4G-1)") (class "Default")
      (node (ref "JP13") (pin "9") (pinfunction "9_9") (pintype "passive"))
      (node (ref "JP3") (pin "7") (pinfunction "7_7") (pintype "passive"))
      (node (ref "RN4") (pin "7") (pinfunction "1_7") (pintype "passive"))
      (node (ref "RN5") (pin "3") (pinfunction "3_3") (pintype "passive"))
    )
    (net (code "134") (name "Net-(RN4H-1)") (class "Default")
      (node (ref "JP13") (pin "10") (pinfunction "10_10") (pintype "passive"))
      (node (ref "JP3") (pin "8") (pinfunction "8_8") (pintype "passive"))
      (node (ref "RN4") (pin "8") (pinfunction "1_8") (pintype "passive"))
      (node (ref "RN5") (pin "2") (pinfunction "2_2") (pintype "passive"))
    )
    (net (code "135") (name "Net-(SJ13-Pad1)") (class "Default")
      (node (ref "SJ13") (pin "1") (pinfunction "1_1") (pintype "passive"))
      (node (ref "U$1") (pin "PB14") (pinfunction "PB14_PB14") (pintype "bidirectional"))
    )
    (net (code "136") (name "Net-(SJ14-Pad1)") (class "Default")
      (node (ref "SJ14") (pin "1") (pinfunction "1_1") (pintype "passive"))
      (node (ref "U$1") (pin "VIN2") (pinfunction "VIN2_VIN2") (pintype "power_in"))
    )
    (net (code "137") (name "OLAT") (class "Default")
      (node (ref "IC3") (pin "12") (pinfunction "RCK_12") (pintype "input"))
      (node (ref "IC5") (pin "12") (pinfunction "RCK_12") (pintype "input"))
      (node (ref "R21") (pin "1") (pinfunction "1_1") (pintype "passive"))
      (node (ref "U$1") (pin "PA8") (pinfunction "PA8_PA8") (pintype "bidirectional"))
    )
    (net (code "138") (name "SCK") (class "Default")
      (node (ref "IC3") (pin "11") (pinfunction "SCK_11") (pintype "input"))
      (node (ref "IC5") (pin "11") (pinfunction "SCK_11") (pintype "input"))
      (node (ref "JP9") (pin "3") (pinfunction "3_3") (pintype "passive"))
      (node (ref "R19") (pin "1") (pinfunction "1_1") (pintype "passive"))
      (node (ref "U$1") (pin "PB3") (pinfunction "PB3_PB3") (pintype "bidirectional"))
    )
    (net (code "139") (name "SCK2") (class "Default")
      (node (ref "IC1") (pin "7") (pinfunction "CLK_7") (pintype "input"))
      (node (ref "IC4") (pin "7") (pinfunction "CLK_7") (pintype "input"))
      (node (ref "U$1") (pin "PB10") (pinfunction "PB10_PB10") (pintype "bidirectional"))
    )
    (net (code "140") (name "SLNK1") (class "Default")
      (node (ref "IC3") (pin "14") (pinfunction "SER_14") (pintype "input"))
      (node (ref "IC5") (pin "9") (pinfunction "QH*_9") (pintype "tri_state"))
      (node (ref "SJ17") (pin "1") (pinfunction "1_1") (pintype "passive"))
    )
    (net (code "141") (name "SLNK2") (class "Default")
      (node (ref "IC3") (pin "9") (pinfunction "QH*_9") (pintype "tri_state"))
      (node (ref "SJ16") (pin "1") (pinfunction "1_1") (pintype "passive"))
    )
    (net (code "142") (name "SRV1") (class "Default")
      (node (ref "JP7") (pin "2") (pinfunction "2_2") (pintype "passive"))
      (node (ref "U$1") (pin "PC9") (pinfunction "PC9_PC9") (pintype "bidirectional"))
    )
    (net (code "143") (name "SRV2") (class "Default")
      (node (ref "JP7") (pin "1") (pinfunction "1_1") (pintype "passive"))
      (node (ref "U$1") (pin "PC7") (pinfunction "PC7_PC7") (pintype "bidirectional"))
    )
    (net (code "144") (name "SRV3") (class "Default")
      (node (ref "JP11") (pin "2") (pinfunction "2_2") (pintype "passive"))
      (node (ref "U$1") (pin "PC8") (pinfunction "PC8_PC8") (pintype "bidirectional"))
    )
    (net (code "145") (name "SRV4") (class "Default")
      (node (ref "JP11") (pin "1") (pinfunction "1_1") (pintype "passive"))
      (node (ref "U$1") (pin "PC6") (pinfunction "PC6_PC6") (pintype "bidirectional"))
    )
    (net (code "146") (name "TIN3") (class "Default")
      (node (ref "IC9") (pin "10") (pinfunction "+IN_10") (pintype "input"))
      (node (ref "U$1") (pin "PB15") (pinfunction "PB15_PB15") (pintype "bidirectional"))
      (node (ref "U$2") (pin "4") (pinfunction "I_4") (pintype "input"))
    )
    (net (code "147") (name "TIN4") (class "Default")
      (node (ref "IC9") (pin "12") (pinfunction "+IN_12") (pintype "input"))
      (node (ref "U$1") (pin "PB12") (pinfunction "PB12_PB12") (pintype "bidirectional"))
      (node (ref "U$3") (pin "2") (pinfunction "I_2") (pintype "input"))
    )
    (net (code "148") (name "V+") (class "Default")
      (node (ref "AP1509") (pin "3") (pinfunction "FB_3") (pintype "bidirectional"))
      (node (ref "C1") (pin "1") (pinfunction "1_1") (pintype "passive"))
      (node (ref "C2") (pin "+") (pinfunction "+_+") (pintype "passive"))
      (node (ref "IC10") (pin "1") (pinfunction "FB_1") (pintype "input"))
      (node (ref "L1") (pin "1") (pinfunction "1_1") (pintype "passive"))
      (node (ref "U$1") (pin "E5V") (pinfunction "E5V_E5V") (pintype "power_in"))
    )
    (net (code "149") (name "unconnected-(H1-MOUNT-PadB3,3)") (class "Default")
      (node (ref "H1") (pin "B3,3") (pinfunction "MOUNT_B3,3") (pintype "passive"))
    )
    (net (code "150") (name "unconnected-(H2-MOUNT-PadB3,3)") (class "Default")
      (node (ref "H2") (pin "B3,3") (pinfunction "MOUNT_B3,3") (pintype "passive"))
    )
    (net (code "151") (name "unconnected-(H3-MOUNT-PadB3,3)") (class "Default")
      (node (ref "H3") (pin "B3,3") (pinfunction "MOUNT_B3,3") (pintype "passive"))
    )
    (net (code "152") (name "unconnected-(H4-MOUNT-PadB3,3)") (class "Default")
      (node (ref "H4") (pin "B3,3") (pinfunction "MOUNT_B3,3") (pintype "passive"))
    )
    (net (code "153") (name "unconnected-(IC7-RS-Pad8)") (class "Default")
      (node (ref "IC7") (pin "8") (pinfunction "RS_8") (pintype "input"))
    )
    (net (code "154") (name "unconnected-(IC7-VREF-Pad5)") (class "Default")
      (node (ref "IC7") (pin "5") (pinfunction "VREF_5") (pintype "output"))
    )
    (net (code "155") (name "unconnected-(J3-Pad2)") (class "Default")
      (node (ref "J3") (pin "2") (pinfunction "2_2") (pintype "passive"))
    )
    (net (code "156") (name "unconnected-(U$1-PadBOOT0)") (class "Default")
      (node (ref "U$1") (pin "BOOT0") (pinfunction "BOOT0_BOOT0") (pintype "bidirectional"))
    )
    (net (code "157") (name "unconnected-(U$1-PadIOREF2)") (class "Default")
      (node (ref "U$1") (pin "IOREF2") (pinfunction "IOREF2_IOREF2") (pintype "input"))
    )
    (net (code "158") (name "unconnected-(U$1-PadNC1-PF7)") (class "Default")
      (node (ref "U$1") (pin "NC1-PF7") (pinfunction "NC1-PF7_NC1-PF7") (pintype "bidirectional"))
    )
    (net (code "159") (name "unconnected-(U$1-PadNC2-PF6)") (class "Default")
      (node (ref "U$1") (pin "NC2-PF6") (pinfunction "NC2-PF6_NC2-PF6") (pintype "bidirectional"))
    )
    (net (code "160") (name "unconnected-(U$1-PadNC3)") (class "Default")
      (node (ref "U$1") (pin "NC3") (pinfunction "NC3_NC3") (pintype "no_connect"))
    )
    (net (code "161") (name "unconnected-(U$1-PadNC4)") (class "Default")
      (node (ref "U$1") (pin "NC4") (pinfunction "NC4_NC4") (pintype "no_connect"))
    )
    (net (code "162") (name "unconnected-(U$1-PadNC5-PD8)") (class "Default")
      (node (ref "U$1") (pin "NC5-PD8") (pinfunction "NC5-PD8_NC5-PD8") (pintype "bidirectional"))
    )
    (net (code "163") (name "unconnected-(U$1-PadNC6-PB11)") (class "Default")
      (node (ref "U$1") (pin "NC6-PB11") (pinfunction "NC6-PB11_NC6-PB11") (pintype "no_connect"))
    )
    (net (code "164") (name "unconnected-(U$1-PadNC7-PF5)") (class "Default")
      (node (ref "U$1") (pin "NC7-PF5") (pinfunction "NC7-PF5_NC7-PF5") (pintype "bidirectional"))
    )
    (net (code "165") (name "unconnected-(U$1-PadNC8-PF4)") (class "Default")
      (node (ref "U$1") (pin "NC8-PF4") (pinfunction "NC8-PF4_NC8-PF4") (pintype "bidirectional"))
    )
    (net (code "166") (name "unconnected-(U$1-PadNRESET)") (class "Default")
      (node (ref "U$1") (pin "NRESET") (pinfunction "NRESET_NRESET") (pintype "input"))
    )
    (net (code "167") (name "unconnected-(U$1-PadPA1)") (class "Default")
      (node (ref "U$1") (pin "PA1") (pinfunction "PA1_PA1") (pintype "bidirectional"))
    )
    (net (code "168") (name "unconnected-(U$1-PadPA2)") (class "Default")
      (node (ref "U$1") (pin "PA2") (pinfunction "PA2_PA2") (pintype "bidirectional"))
    )
    (net (code "169") (name "unconnected-(U$1-PadPA3)") (class "Default")
      (node (ref "U$1") (pin "PA3") (pinfunction "PA3_PA3") (pintype "bidirectional"))
    )
    (net (code "170") (name "unconnected-(U$1-PadPA5)") (class "Default")
      (node (ref "U$1") (pin "PA5") (pinfunction "PA5_PA5") (pintype "bidirectional"))
    )
    (net (code "171") (name "unconnected-(U$1-PadPA7)") (class "Default")
      (node (ref "U$1") (pin "PA7") (pinfunction "PA7_PA7") (pintype "bidirectional"))
    )
    (net (code "172") (name "unconnected-(U$1-PadPA9)") (class "Default")
      (node (ref "U$1") (pin "PA9") (pinfunction "PA9_PA9") (pintype "bidirectional"))
    )
    (net (code "173") (name "unconnected-(U$1-PadPA10)") (class "Default")
      (node (ref "U$1") (pin "PA10") (pinfunction "PA10_PA10") (pintype "bidirectional"))
    )
    (net (code "174") (name "unconnected-(U$1-PadPA11)") (class "Default")
      (node (ref "U$1") (pin "PA11") (pinfunction "PA11_PA11") (pintype "bidirectional"))
    )
    (net (code "175") (name "unconnected-(U$1-PadPA12)") (class "Default")
      (node (ref "U$1") (pin "PA12") (pinfunction "PA12_PA12") (pintype "bidirectional"))
    )
    (net (code "176") (name "unconnected-(U$1-PadPA13)") (class "Default")
      (node (ref "U$1") (pin "PA13") (pinfunction "PA13_PA13") (pintype "bidirectional"))
    )
    (net (code "177") (name "unconnected-(U$1-PadPA14)") (class "Default")
      (node (ref "U$1") (pin "PA14") (pinfunction "PA14_PA14") (pintype "bidirectional"))
    )
    (net (code "178") (name "unconnected-(U$1-PadPB0)") (class "Default")
      (node (ref "U$1") (pin "PB0") (pinfunction "PB0_PB0") (pintype "bidirectional"))
    )
    (net (code "179") (name "unconnected-(U$1-PadPB13)") (class "Default")
      (node (ref "U$1") (pin "PB13") (pinfunction "PB13_PB13") (pintype "bidirectional"))
    )
    (net (code "180") (name "unconnected-(U$1-PadPC1)") (class "Default")
      (node (ref "U$1") (pin "PC1") (pinfunction "PC1_PC1") (pintype "bidirectional"))
    )
    (net (code "181") (name "unconnected-(U$1-PadPC4)") (class "Default")
      (node (ref "U$1") (pin "PC4") (pinfunction "PC4_PC4") (pintype "bidirectional"))
    )
    (net (code "182") (name "unconnected-(U$1-PadPC5)") (class "Default")
      (node (ref "U$1") (pin "PC5") (pinfunction "PC5_PC5") (pintype "bidirectional"))
    )
    (net (code "183") (name "unconnected-(U$1-PadPC13)") (class "Default")
      (node (ref "U$1") (pin "PC13") (pinfunction "PC13_PC13") (pintype "bidirectional"))
    )
    (net (code "184") (name "unconnected-(U$1-PadPC14)") (class "Default")
      (node (ref "U$1") (pin "PC14") (pinfunction "PC14_PC14") (pintype "bidirectional"))
    )
    (net (code "185") (name "unconnected-(U$1-PadPC15)") (class "Default")
      (node (ref "U$1") (pin "PC15") (pinfunction "PC15_PC15") (pintype "bidirectional"))
    )
    (net (code "186") (name "unconnected-(U$1-PadPF0-PH0)") (class "Default")
      (node (ref "U$1") (pin "PF0-PH0") (pinfunction "PF0-PH0_PF0-PH0") (pintype "bidirectional"))
    )
  )
)
